# Copy_of_testboard_chip1_bk.net
KiCad netlist of a schematic drawn in Altium Designer
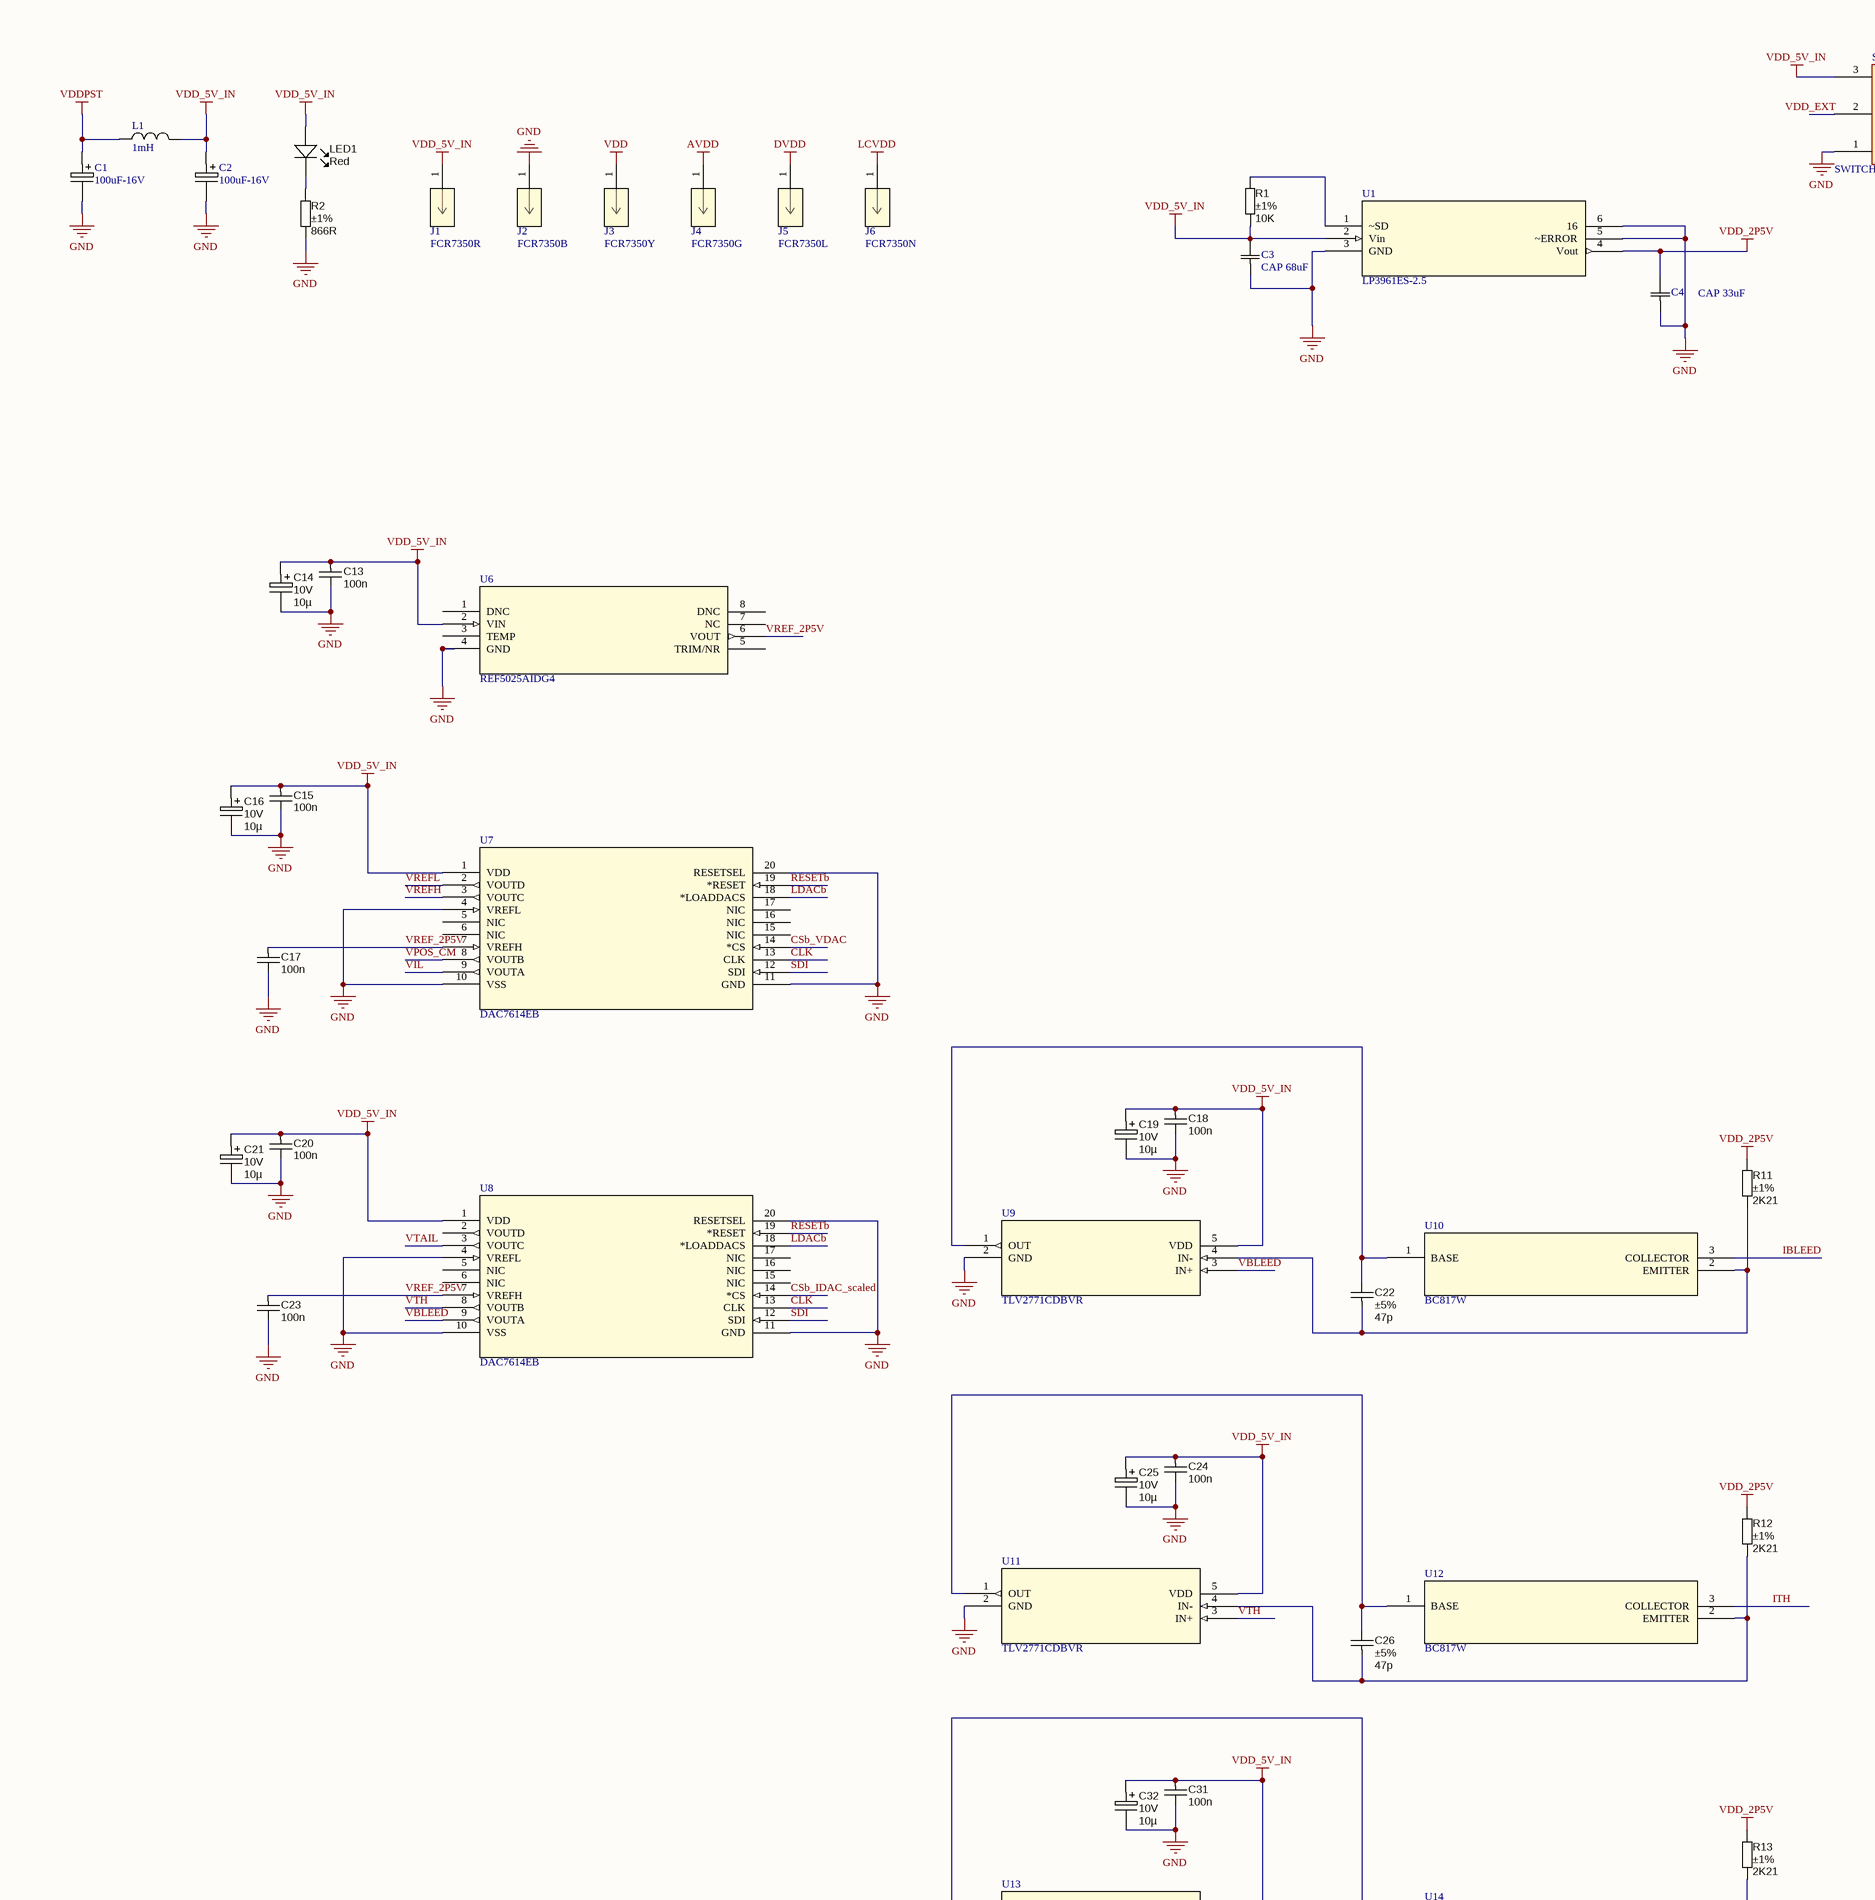
[diagram p0: Copy of testboard_chip1_bk.SchDoc, top left]
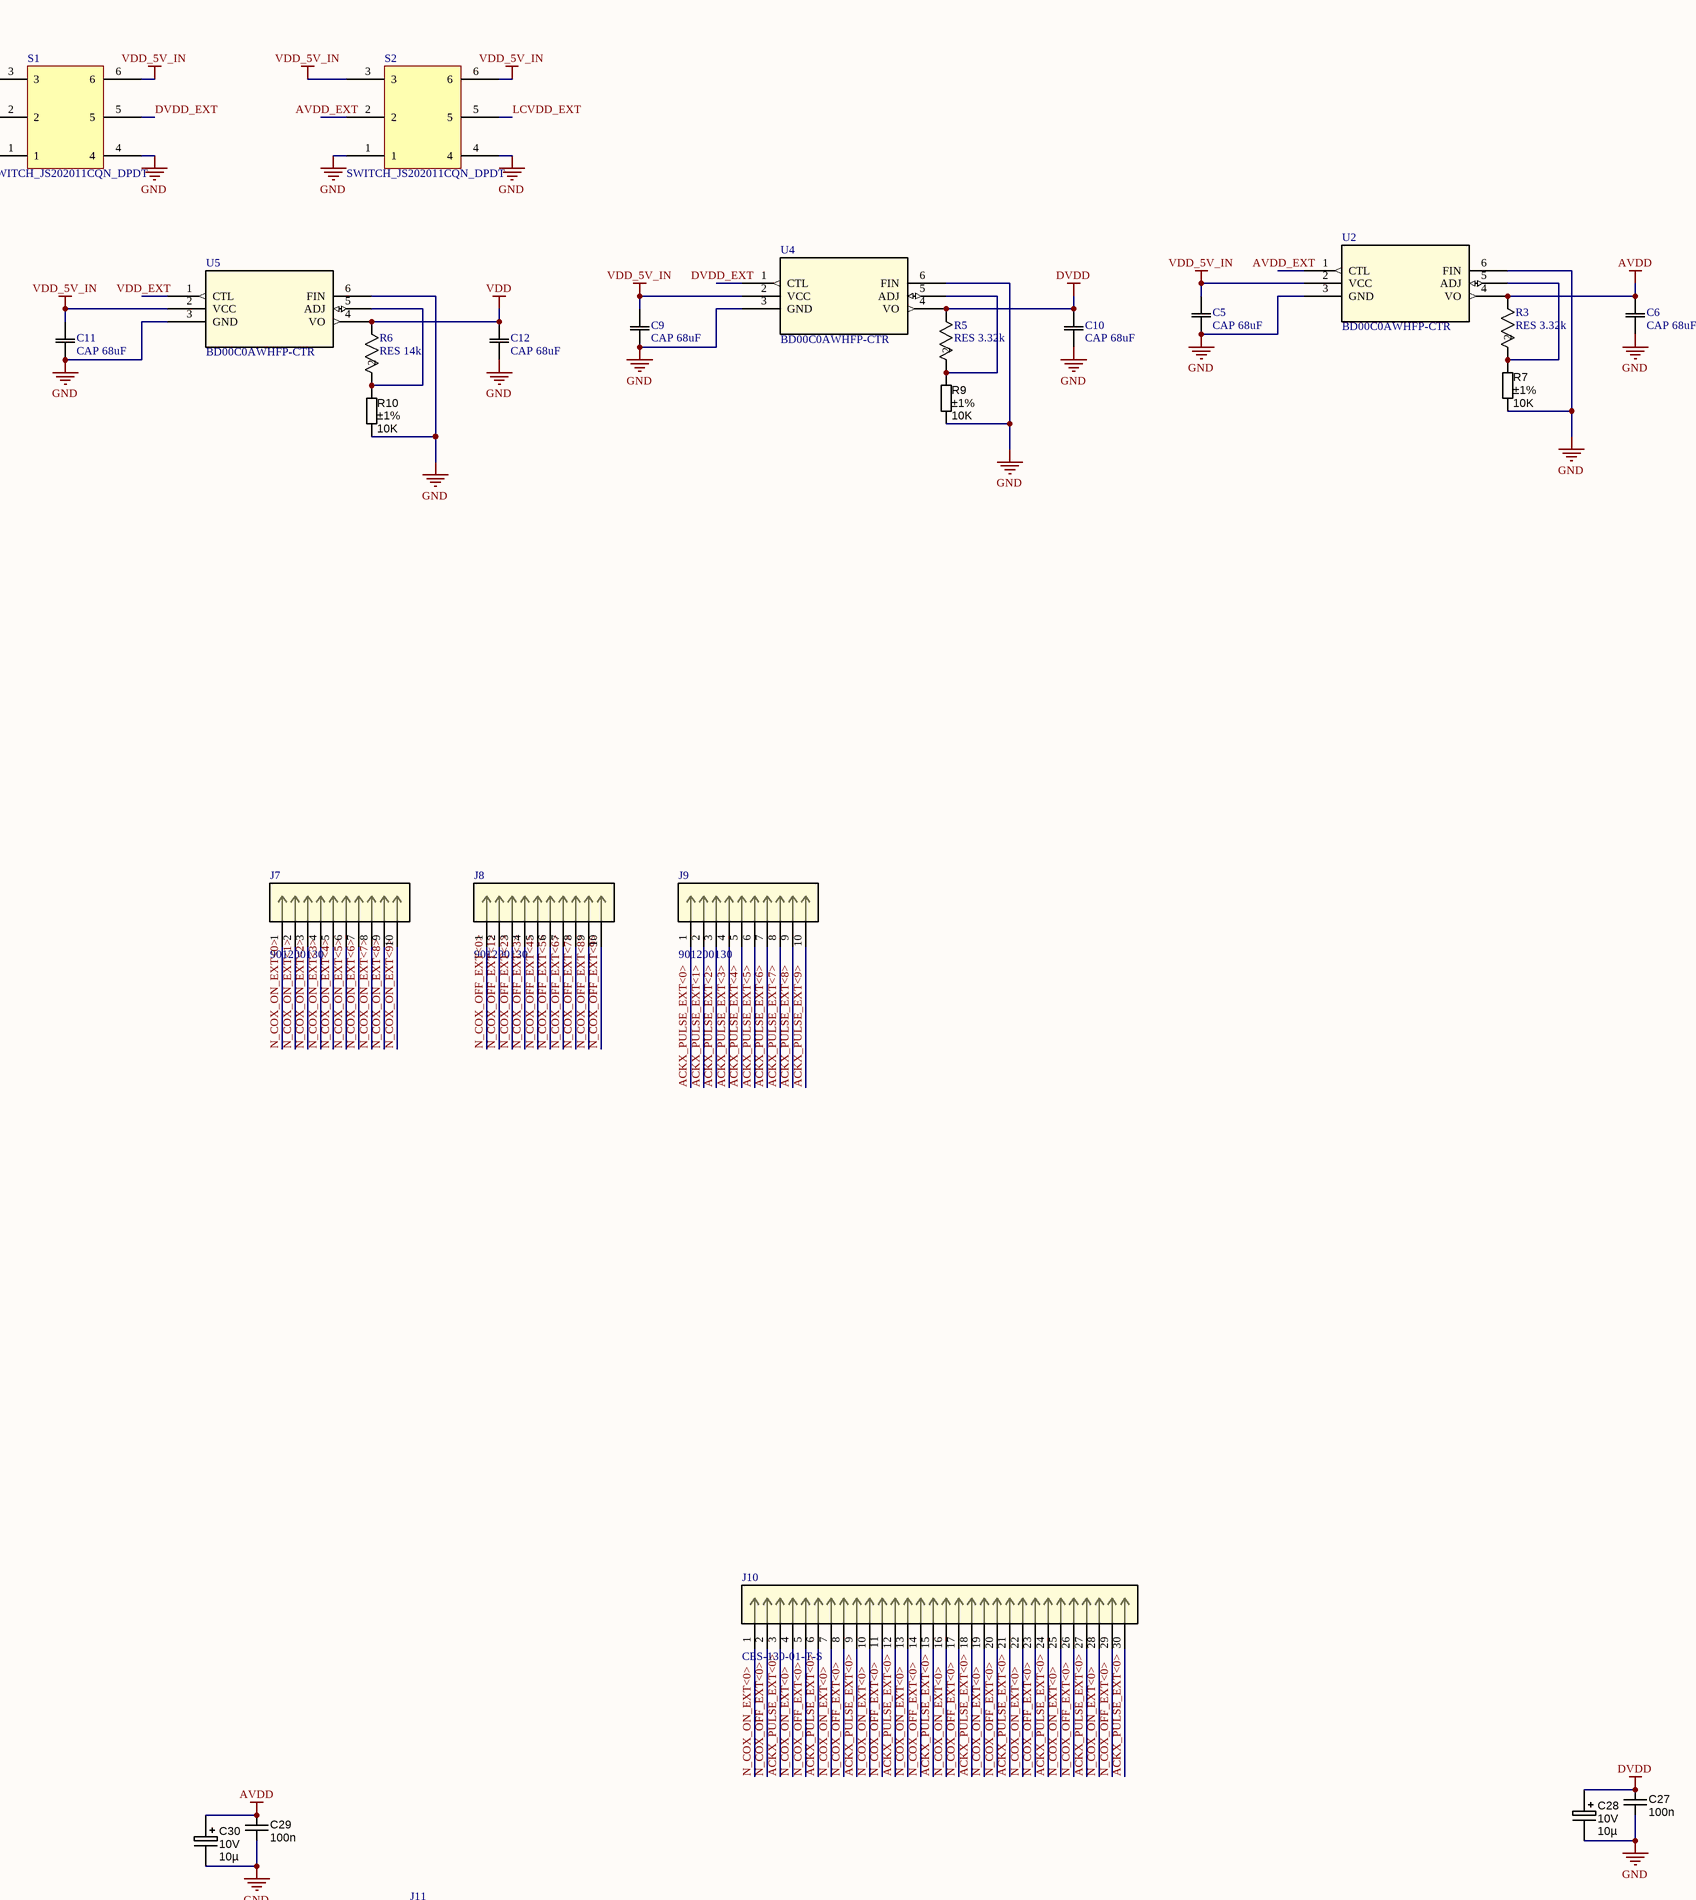
[diagram p1: Copy of testboard_chip1_bk.SchDoc, top middle]
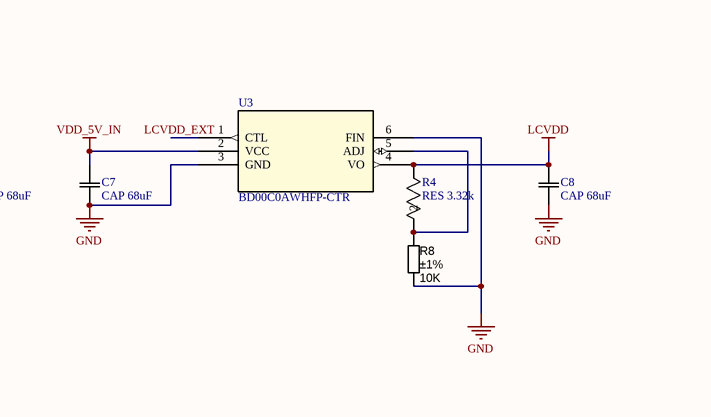
[diagram p2: Copy of testboard_chip1_bk.SchDoc, top right]
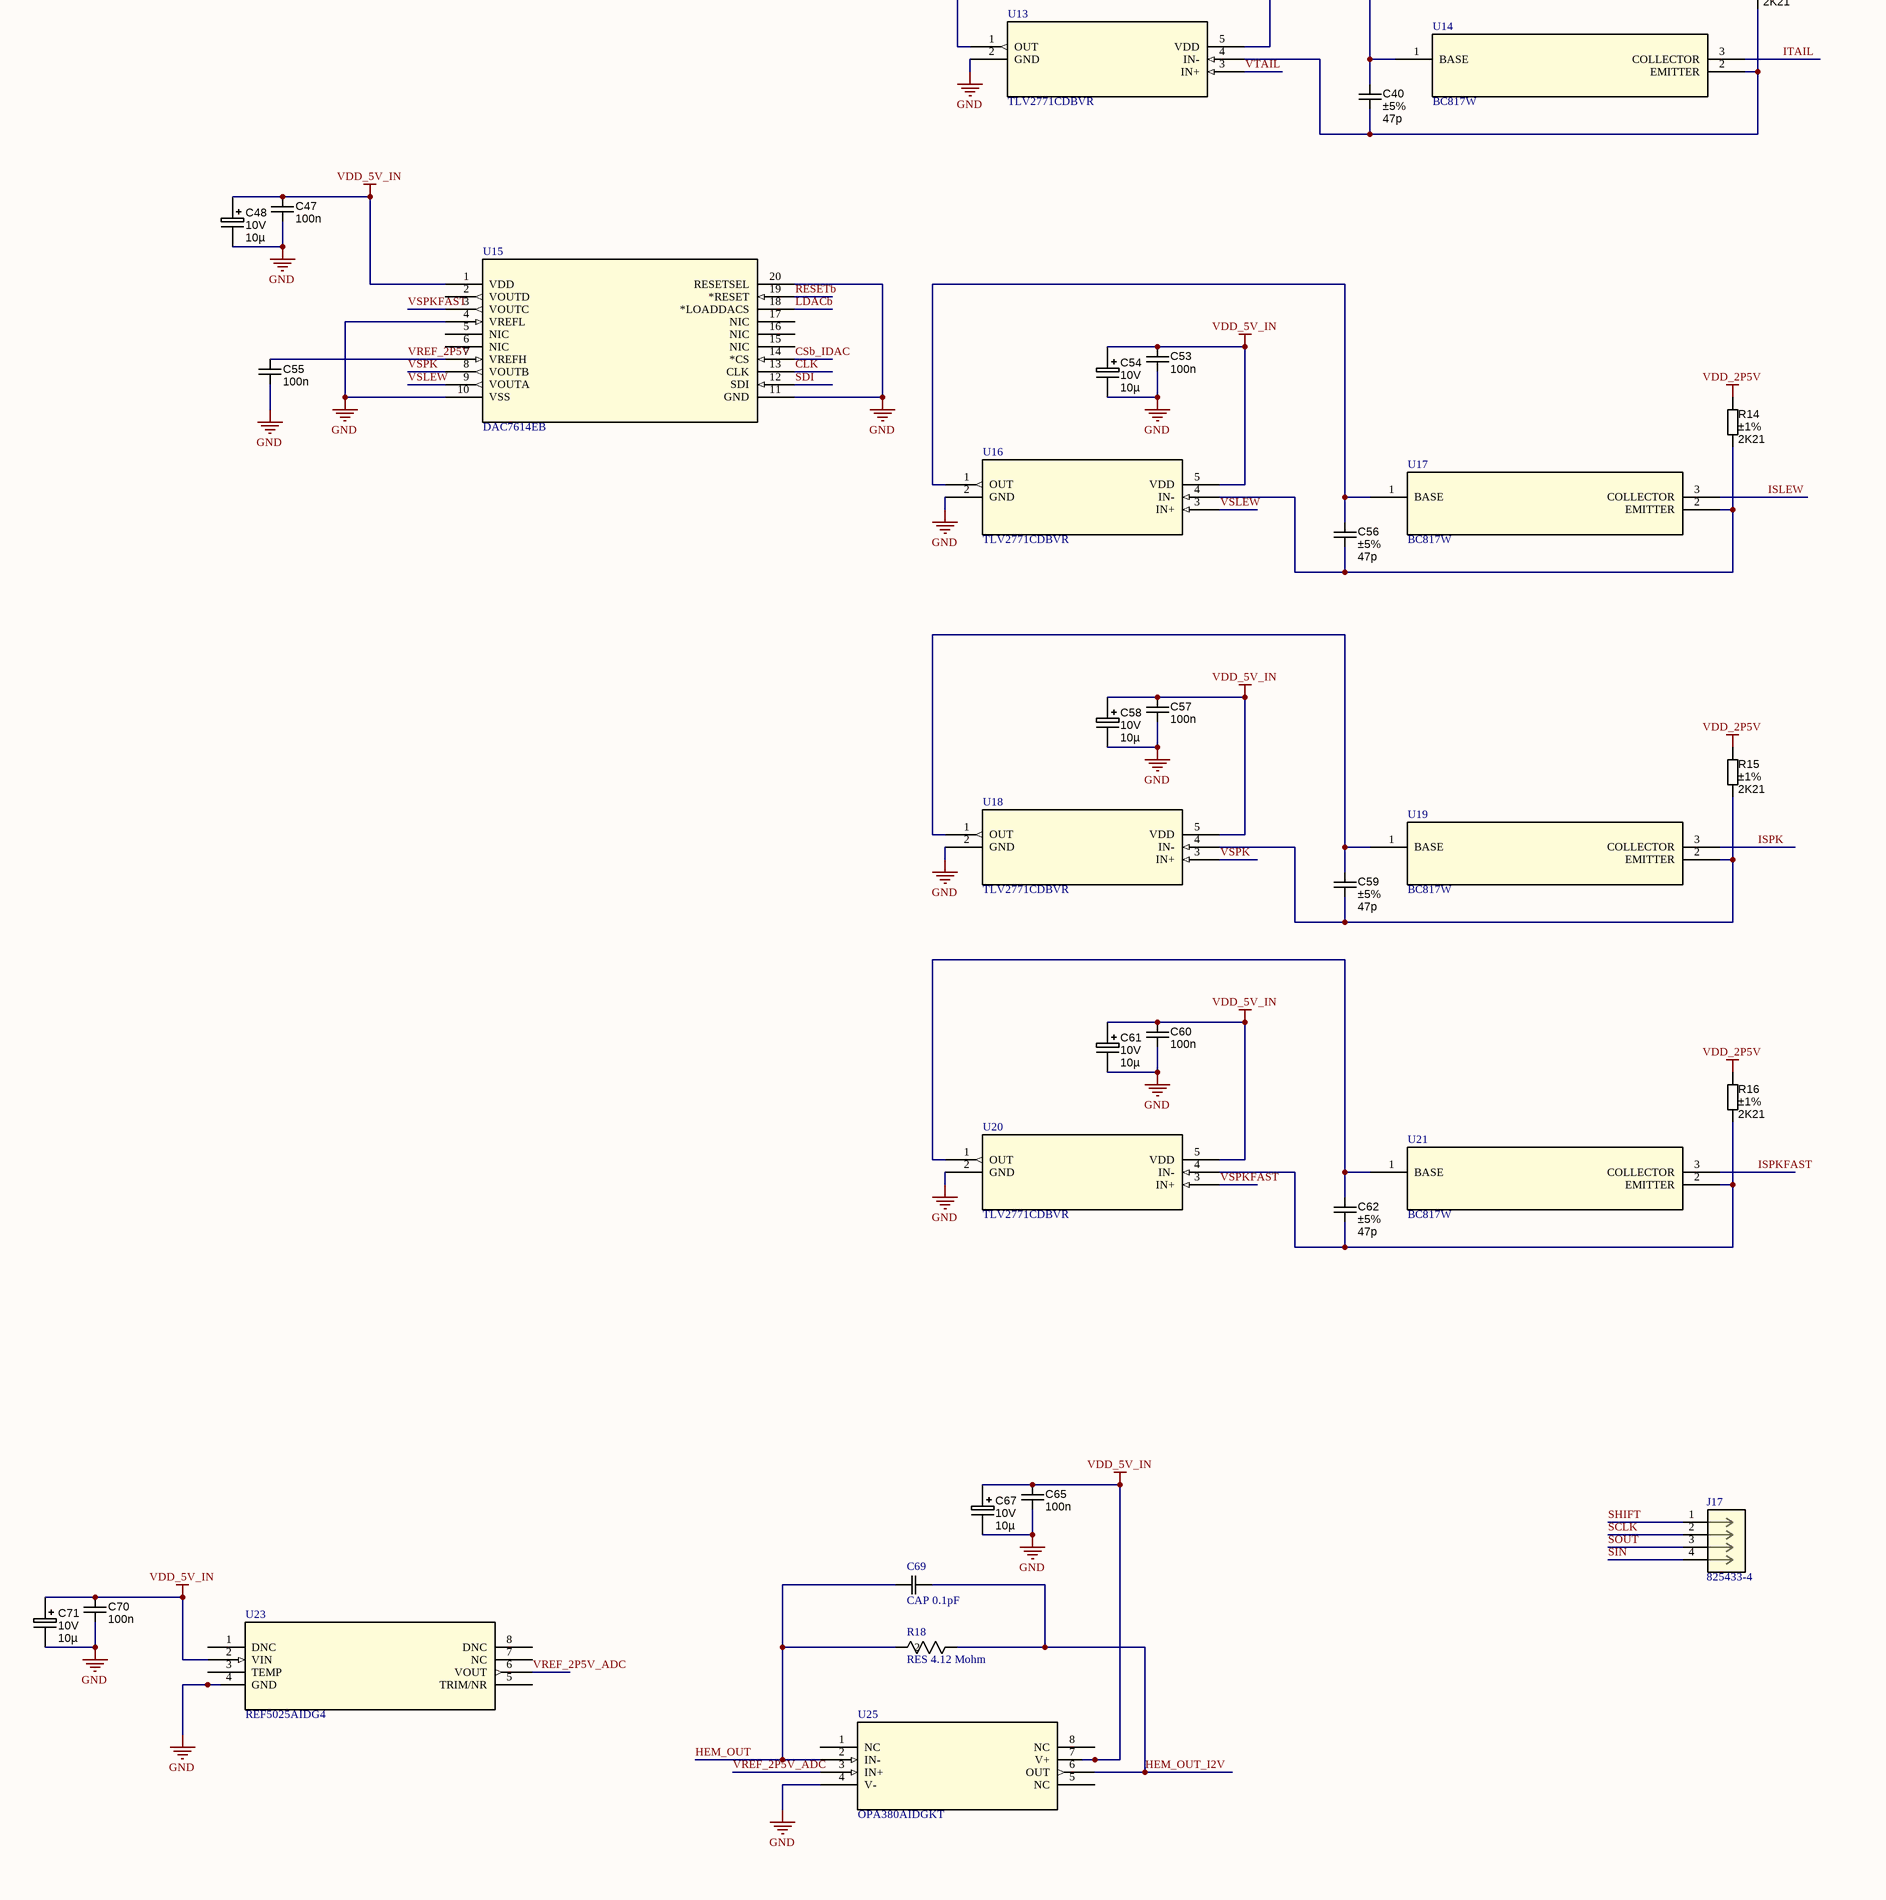
[diagram p3: Copy of testboard_chip1_bk.SchDoc, bottom left]
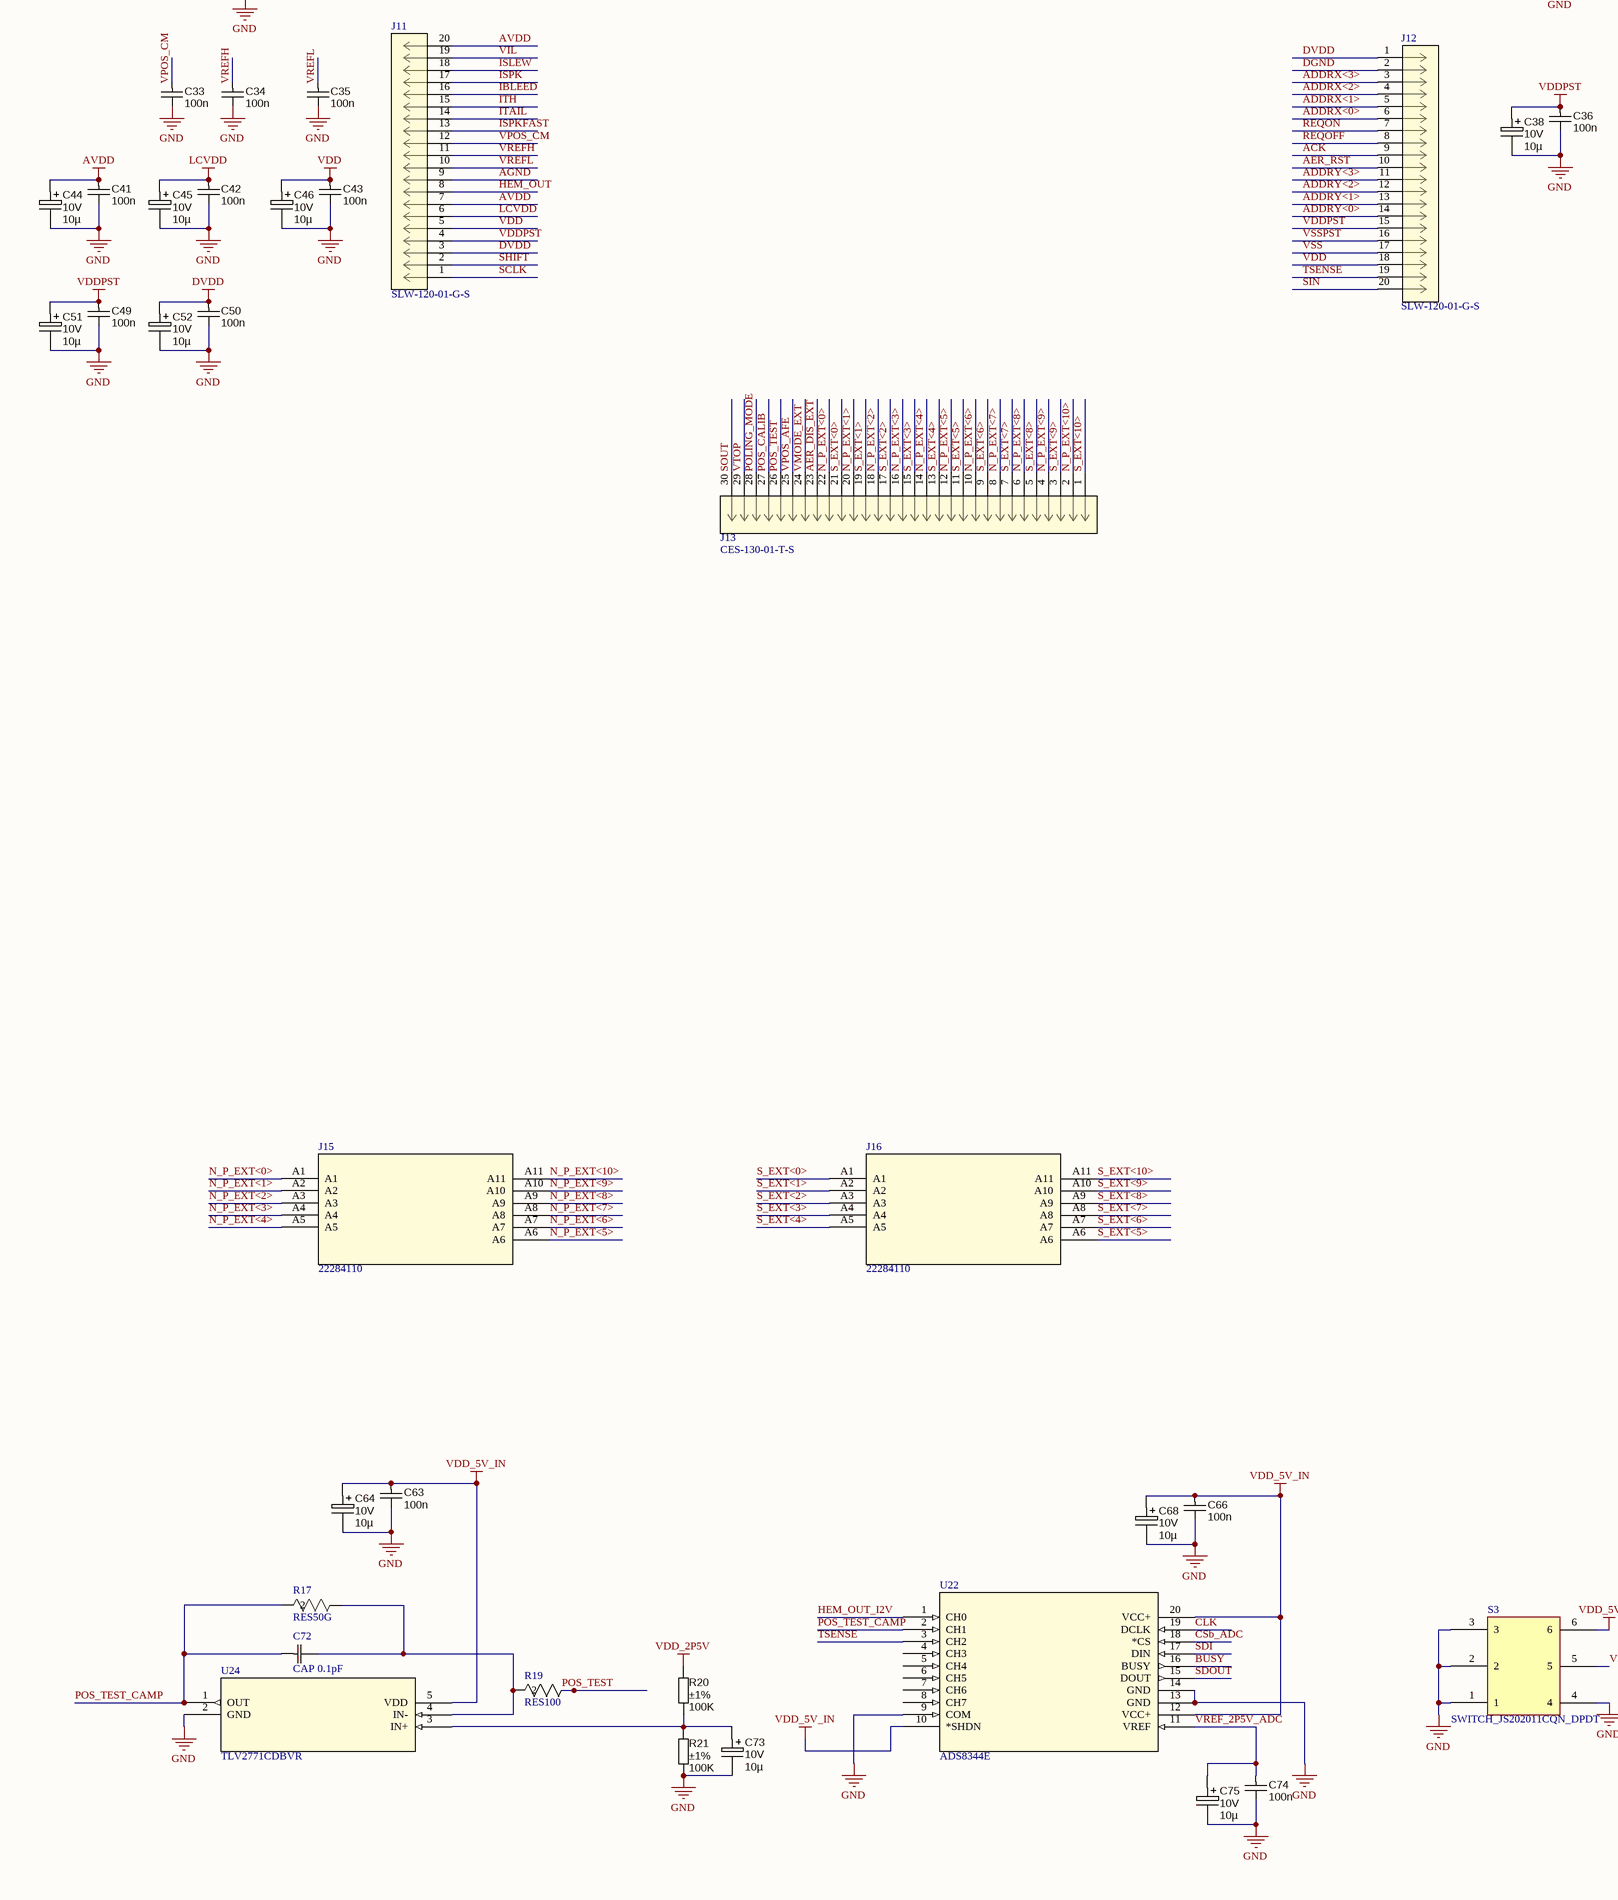
[diagram p4: Copy of testboard_chip1_bk.SchDoc, bottom middle]
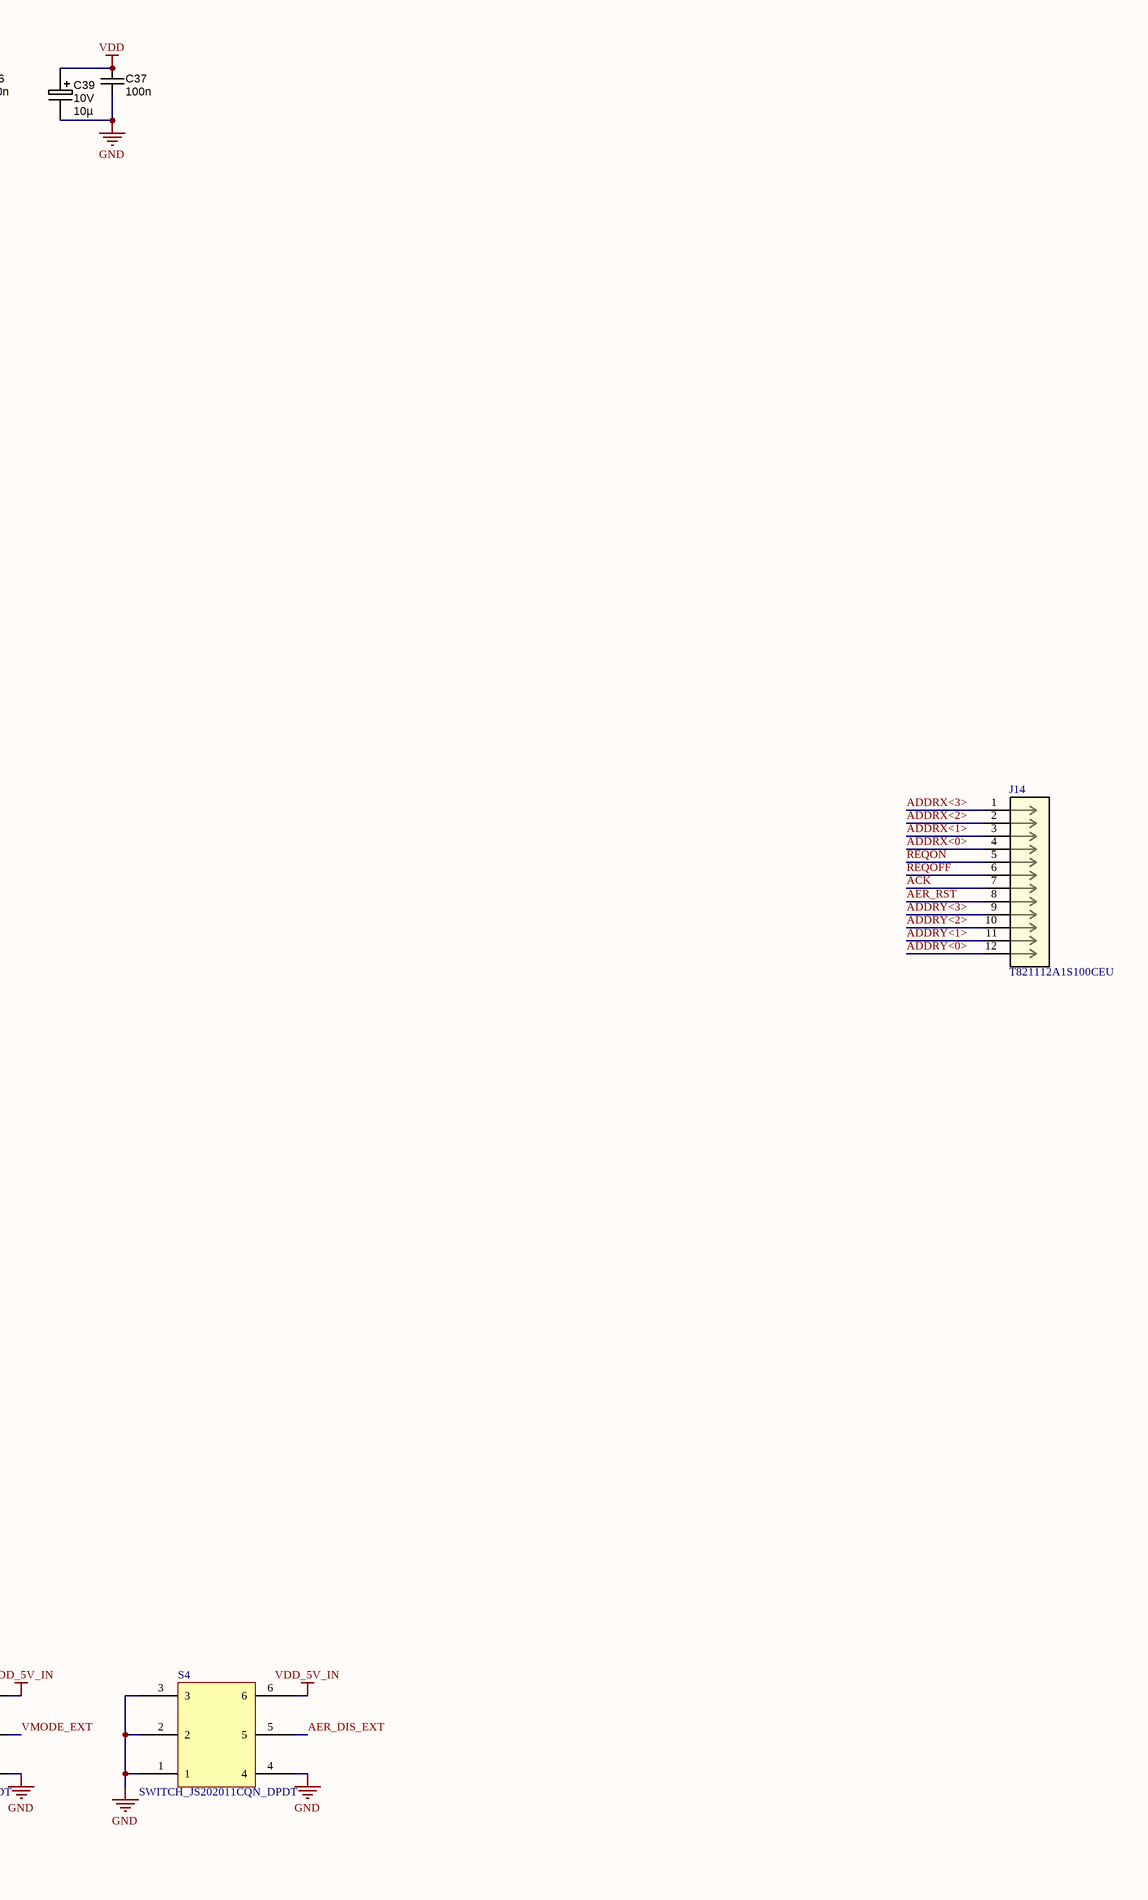
[diagram p5: Copy of testboard_chip1_bk.SchDoc, bottom right]

(export (version "E")
  (design (tool "Eeschema 10.0.6"))
  (components
    (comp (ref "C1")
      (value "100uF-16V")
      (footprint "PANACAP-D-GENERIC")
      (description "GENERIC CAPACITOR POLARISED")
      (libsource (lib "vh_altium_library") (part "PANACAP-100UF-16V-FK"))
    )
    (comp (ref "C2")
      (value "100uF-16V")
      (footprint "PANACAP-D-GENERIC")
      (description "GENERIC CAPACITOR POLARISED")
      (libsource (lib "vh_altium_library") (part "PANACAP-100UF-16V-FK"))
    )
    (comp (ref "C3")
      (value "CAP 68uF")
      (footprint "CAP_3216_TDK")
      (description "No Description Available")
      (fields
        (field (name "MANUFACTURER_PART_NUMBER") "C3216X5R1A686M160AC")
        (field (name "COPYRIGHT") "Copyright (C) 2022 Ultra Librarian. All rights reserved.")
      )
      (libsource (lib "C3216X5R1A686M160AC") (part "C3216X5R1A686M160AC"))
    )
    (comp (ref "C4")
      (value "CAP 33uF")
      (footprint "CAP_4532_TDK")
      (description "No Description Available")
      (fields
        (field (name "MANUFACTURER_PART_NUMBER") "C4532X7R1C336M250KC")
        (field (name "COPYRIGHT") "Copyright (C) 2022 Ultra Librarian. All rights reserved.")
      )
      (libsource (lib "C4532X7R1C336M250KC") (part "C4532X7R1C336M250KC"))
    )
    (comp (ref "C5")
      (value "CAP 68uF")
      (footprint "CAP_3216_TDK")
      (description "No Description Available")
      (fields
        (field (name "MANUFACTURER_PART_NUMBER") "C3216X5R1A686M160AC")
        (field (name "COPYRIGHT") "Copyright (C) 2022 Ultra Librarian. All rights reserved.")
      )
      (libsource (lib "C3216X5R1A686M160AC") (part "C3216X5R1A686M160AC"))
    )
    (comp (ref "C6")
      (value "CAP 68uF")
      (footprint "CAP_3216_TDK")
      (description "No Description Available")
      (fields
        (field (name "MANUFACTURER_PART_NUMBER") "C3216X5R1A686M160AC")
        (field (name "COPYRIGHT") "Copyright (C) 2022 Ultra Librarian. All rights reserved.")
      )
      (libsource (lib "C3216X5R1A686M160AC") (part "C3216X5R1A686M160AC"))
    )
    (comp (ref "C7")
      (value "CAP 68uF")
      (footprint "CAP_3216_TDK")
      (description "No Description Available")
      (fields
        (field (name "MANUFACTURER_PART_NUMBER") "C3216X5R1A686M160AC")
        (field (name "COPYRIGHT") "Copyright (C) 2022 Ultra Librarian. All rights reserved.")
      )
      (libsource (lib "C3216X5R1A686M160AC") (part "C3216X5R1A686M160AC"))
    )
    (comp (ref "C8")
      (value "CAP 68uF")
      (footprint "CAP_3216_TDK")
      (description "No Description Available")
      (fields
        (field (name "MANUFACTURER_PART_NUMBER") "C3216X5R1A686M160AC")
        (field (name "COPYRIGHT") "Copyright (C) 2022 Ultra Librarian. All rights reserved.")
      )
      (libsource (lib "C3216X5R1A686M160AC") (part "C3216X5R1A686M160AC"))
    )
    (comp (ref "C9")
      (value "CAP 68uF")
      (footprint "CAP_3216_TDK")
      (description "No Description Available")
      (fields
        (field (name "MANUFACTURER_PART_NUMBER") "C3216X5R1A686M160AC")
        (field (name "COPYRIGHT") "Copyright (C) 2022 Ultra Librarian. All rights reserved.")
      )
      (libsource (lib "C3216X5R1A686M160AC") (part "C3216X5R1A686M160AC"))
    )
    (comp (ref "C10")
      (value "CAP 68uF")
      (footprint "CAP_3216_TDK")
      (description "No Description Available")
      (fields
        (field (name "MANUFACTURER_PART_NUMBER") "C3216X5R1A686M160AC")
        (field (name "COPYRIGHT") "Copyright (C) 2022 Ultra Librarian. All rights reserved.")
      )
      (libsource (lib "C3216X5R1A686M160AC") (part "C3216X5R1A686M160AC"))
    )
    (comp (ref "C11")
      (value "CAP 68uF")
      (footprint "CAP_3216_TDK")
      (description "No Description Available")
      (fields
        (field (name "MANUFACTURER_PART_NUMBER") "C3216X5R1A686M160AC")
        (field (name "COPYRIGHT") "Copyright (C) 2022 Ultra Librarian. All rights reserved.")
      )
      (libsource (lib "C3216X5R1A686M160AC") (part "C3216X5R1A686M160AC"))
    )
    (comp (ref "C12")
      (value "CAP 68uF")
      (footprint "CAP_3216_TDK")
      (description "No Description Available")
      (fields
        (field (name "MANUFACTURER_PART_NUMBER") "C3216X5R1A686M160AC")
        (field (name "COPYRIGHT") "Copyright (C) 2022 Ultra Librarian. All rights reserved.")
      )
      (libsource (lib "C3216X5R1A686M160AC") (part "C3216X5R1A686M160AC"))
    )
    (comp (ref "C13")
      (value "100n")
      (footprint "CAPC1608N")
      (description "Capacitor SMD Cer 100nF 10% 50V X7R 0603")
      (fields (field (name "TOLERANCE") "±10%") (field (name "Comment") "approved sub OK"))
      (libsource (lib "PBL - Capacitors") (part "CAPC_100n_0603"))
    )
    (comp (ref "C14")
      (value "10µ")
      (footprint "CAPMP2012X150USR")
      (description "Capacitor SMD Tantalum 10uF 20% 10V 0805")
      (fields (field (name "TOLERANCE") "±20%") (field (name "RATINGS") "10V"))
      (libsource (lib "PBL - Capacitors") (part "CAPT_10u_0805_10V"))
    )
    (comp (ref "C15")
      (value "100n")
      (footprint "CAPC1608N")
      (description "Capacitor SMD Cer 100nF 10% 50V X7R 0603")
      (fields (field (name "TOLERANCE") "±10%") (field (name "Comment") "approved sub OK"))
      (libsource (lib "PBL - Capacitors") (part "CAPC_100n_0603"))
    )
    (comp (ref "C16")
      (value "10µ")
      (footprint "CAPMP2012X150USR")
      (description "Capacitor SMD Tantalum 10uF 20% 10V 0805")
      (fields (field (name "TOLERANCE") "±20%") (field (name "RATINGS") "10V"))
      (libsource (lib "PBL - Capacitors") (part "CAPT_10u_0805_10V"))
    )
    (comp (ref "C17")
      (value "100n")
      (footprint "CAPC1608N")
      (description "Capacitor SMD Cer 100nF 10% 50V X7R 0603")
      (fields (field (name "TOLERANCE") "±10%") (field (name "Comment") "approved sub OK"))
      (libsource (lib "PBL - Capacitors") (part "CAPC_100n_0603"))
    )
    (comp (ref "C18")
      (value "100n")
      (footprint "CAPC1608N")
      (description "Capacitor SMD Cer 100nF 10% 50V X7R 0603")
      (fields (field (name "TOLERANCE") "±10%") (field (name "Comment") "approved sub OK"))
      (libsource (lib "PBL - Capacitors") (part "CAPC_100n_0603"))
    )
    (comp (ref "C19")
      (value "10µ")
      (footprint "CAPMP2012X150USR")
      (description "Capacitor SMD Tantalum 10uF 20% 10V 0805")
      (fields (field (name "TOLERANCE") "±20%") (field (name "RATINGS") "10V"))
      (libsource (lib "PBL - Capacitors") (part "CAPT_10u_0805_10V"))
    )
    (comp (ref "C20")
      (value "100n")
      (footprint "CAPC1608N")
      (description "Capacitor SMD Cer 100nF 10% 50V X7R 0603")
      (fields (field (name "TOLERANCE") "±10%") (field (name "Comment") "approved sub OK"))
      (libsource (lib "PBL - Capacitors") (part "CAPC_100n_0603"))
    )
    (comp (ref "C21")
      (value "10µ")
      (footprint "CAPMP2012X150USR")
      (description "Capacitor SMD Tantalum 10uF 20% 10V 0805")
      (fields (field (name "TOLERANCE") "±20%") (field (name "RATINGS") "10V"))
      (libsource (lib "PBL - Capacitors") (part "CAPT_10u_0805_10V"))
    )
    (comp (ref "C22")
      (value "47p")
      (footprint "CAPC1608N")
      (description "Capacitor SMD Cer 47pF 0603")
      (fields (field (name "TOLERANCE") "±5%"))
      (libsource (lib "MB - Misc") (part "CAPC_47p_0603"))
    )
    (comp (ref "C23")
      (value "100n")
      (footprint "CAPC1608N")
      (description "Capacitor SMD Cer 100nF 10% 50V X7R 0603")
      (fields (field (name "TOLERANCE") "±10%") (field (name "Comment") "approved sub OK"))
      (libsource (lib "PBL - Capacitors") (part "CAPC_100n_0603"))
    )
    (comp (ref "C24")
      (value "100n")
      (footprint "CAPC1608N")
      (description "Capacitor SMD Cer 100nF 10% 50V X7R 0603")
      (fields (field (name "TOLERANCE") "±10%") (field (name "Comment") "approved sub OK"))
      (libsource (lib "PBL - Capacitors") (part "CAPC_100n_0603"))
    )
    (comp (ref "C25")
      (value "10µ")
      (footprint "CAPMP2012X150USR")
      (description "Capacitor SMD Tantalum 10uF 20% 10V 0805")
      (fields (field (name "TOLERANCE") "±20%") (field (name "RATINGS") "10V"))
      (libsource (lib "PBL - Capacitors") (part "CAPT_10u_0805_10V"))
    )
    (comp (ref "C26")
      (value "47p")
      (footprint "CAPC1608N")
      (description "Capacitor SMD Cer 47pF 0603")
      (fields (field (name "TOLERANCE") "±5%"))
      (libsource (lib "MB - Misc") (part "CAPC_47p_0603"))
    )
    (comp (ref "C27")
      (value "100n")
      (footprint "CAPC1608N")
      (description "Capacitor SMD Cer 100nF 10% 50V X7R 0603")
      (fields (field (name "TOLERANCE") "±10%") (field (name "Comment") "approved sub OK"))
      (libsource (lib "PBL - Capacitors") (part "CAPC_100n_0603"))
    )
    (comp (ref "C28")
      (value "10µ")
      (footprint "CAPMP2012X150USR")
      (description "Capacitor SMD Tantalum 10uF 20% 10V 0805")
      (fields (field (name "TOLERANCE") "±20%") (field (name "RATINGS") "10V"))
      (libsource (lib "PBL - Capacitors") (part "CAPT_10u_0805_10V"))
    )
    (comp (ref "C29")
      (value "100n")
      (footprint "CAPC1608N")
      (description "Capacitor SMD Cer 100nF 10% 50V X7R 0603")
      (fields (field (name "TOLERANCE") "±10%") (field (name "Comment") "approved sub OK"))
      (libsource (lib "PBL - Capacitors") (part "CAPC_100n_0603"))
    )
    (comp (ref "C30")
      (value "10µ")
      (footprint "CAPMP2012X150USR")
      (description "Capacitor SMD Tantalum 10uF 20% 10V 0805")
      (fields (field (name "TOLERANCE") "±20%") (field (name "RATINGS") "10V"))
      (libsource (lib "PBL - Capacitors") (part "CAPT_10u_0805_10V"))
    )
    (comp (ref "C31")
      (value "100n")
      (footprint "CAPC1608N")
      (description "Capacitor SMD Cer 100nF 10% 50V X7R 0603")
      (fields (field (name "TOLERANCE") "±10%") (field (name "Comment") "approved sub OK"))
      (libsource (lib "PBL - Capacitors") (part "CAPC_100n_0603"))
    )
    (comp (ref "C32")
      (value "10µ")
      (footprint "CAPMP2012X150USR")
      (description "Capacitor SMD Tantalum 10uF 20% 10V 0805")
      (fields (field (name "TOLERANCE") "±20%") (field (name "RATINGS") "10V"))
      (libsource (lib "PBL - Capacitors") (part "CAPT_10u_0805_10V"))
    )
    (comp (ref "C33")
      (value "100n")
      (footprint "CAPC1608N")
      (description "Capacitor SMD Cer 100nF 10% 50V X7R 0603")
      (fields (field (name "TOLERANCE") "±10%") (field (name "Comment") "approved sub OK"))
      (libsource (lib "PBL - Capacitors") (part "CAPC_100n_0603"))
    )
    (comp (ref "C34")
      (value "100n")
      (footprint "CAPC1608N")
      (description "Capacitor SMD Cer 100nF 10% 50V X7R 0603")
      (fields (field (name "TOLERANCE") "±10%") (field (name "Comment") "approved sub OK"))
      (libsource (lib "PBL - Capacitors") (part "CAPC_100n_0603"))
    )
    (comp (ref "C35")
      (value "100n")
      (footprint "CAPC1608N")
      (description "Capacitor SMD Cer 100nF 10% 50V X7R 0603")
      (fields (field (name "TOLERANCE") "±10%") (field (name "Comment") "approved sub OK"))
      (libsource (lib "PBL - Capacitors") (part "CAPC_100n_0603"))
    )
    (comp (ref "C36")
      (value "100n")
      (footprint "CAPC1608N")
      (description "Capacitor SMD Cer 100nF 10% 50V X7R 0603")
      (fields (field (name "TOLERANCE") "±10%") (field (name "Comment") "approved sub OK"))
      (libsource (lib "PBL - Capacitors") (part "CAPC_100n_0603"))
    )
    (comp (ref "C37")
      (value "100n")
      (footprint "CAPC1608N")
      (description "Capacitor SMD Cer 100nF 10% 50V X7R 0603")
      (fields (field (name "TOLERANCE") "±10%") (field (name "Comment") "approved sub OK"))
      (libsource (lib "PBL - Capacitors") (part "CAPC_100n_0603"))
    )
    (comp (ref "C38")
      (value "10µ")
      (footprint "CAPMP2012X150USR")
      (description "Capacitor SMD Tantalum 10uF 20% 10V 0805")
      (fields (field (name "TOLERANCE") "±20%") (field (name "RATINGS") "10V"))
      (libsource (lib "PBL - Capacitors") (part "CAPT_10u_0805_10V"))
    )
    (comp (ref "C39")
      (value "10µ")
      (footprint "CAPMP2012X150USR")
      (description "Capacitor SMD Tantalum 10uF 20% 10V 0805")
      (fields (field (name "TOLERANCE") "±20%") (field (name "RATINGS") "10V"))
      (libsource (lib "PBL - Capacitors") (part "CAPT_10u_0805_10V"))
    )
    (comp (ref "C40")
      (value "47p")
      (footprint "CAPC1608N")
      (description "Capacitor SMD Cer 47pF 0603")
      (fields (field (name "TOLERANCE") "±5%"))
      (libsource (lib "MB - Misc") (part "CAPC_47p_0603"))
    )
    (comp (ref "C41")
      (value "100n")
      (footprint "CAPC1608N")
      (description "Capacitor SMD Cer 100nF 10% 50V X7R 0603")
      (fields (field (name "TOLERANCE") "±10%") (field (name "Comment") "approved sub OK"))
      (libsource (lib "PBL - Capacitors") (part "CAPC_100n_0603"))
    )
    (comp (ref "C42")
      (value "100n")
      (footprint "CAPC1608N")
      (description "Capacitor SMD Cer 100nF 10% 50V X7R 0603")
      (fields (field (name "TOLERANCE") "±10%") (field (name "Comment") "approved sub OK"))
      (libsource (lib "PBL - Capacitors") (part "CAPC_100n_0603"))
    )
    (comp (ref "C43")
      (value "100n")
      (footprint "CAPC1608N")
      (description "Capacitor SMD Cer 100nF 10% 50V X7R 0603")
      (fields (field (name "TOLERANCE") "±10%") (field (name "Comment") "approved sub OK"))
      (libsource (lib "PBL - Capacitors") (part "CAPC_100n_0603"))
    )
    (comp (ref "C44")
      (value "10µ")
      (footprint "CAPMP2012X150USR")
      (description "Capacitor SMD Tantalum 10uF 20% 10V 0805")
      (fields (field (name "TOLERANCE") "±20%") (field (name "RATINGS") "10V"))
      (libsource (lib "PBL - Capacitors") (part "CAPT_10u_0805_10V"))
    )
    (comp (ref "C45")
      (value "10µ")
      (footprint "CAPMP2012X150USR")
      (description "Capacitor SMD Tantalum 10uF 20% 10V 0805")
      (fields (field (name "TOLERANCE") "±20%") (field (name "RATINGS") "10V"))
      (libsource (lib "PBL - Capacitors") (part "CAPT_10u_0805_10V"))
    )
    (comp (ref "C46")
      (value "10µ")
      (footprint "CAPMP2012X150USR")
      (description "Capacitor SMD Tantalum 10uF 20% 10V 0805")
      (fields (field (name "TOLERANCE") "±20%") (field (name "RATINGS") "10V"))
      (libsource (lib "PBL - Capacitors") (part "CAPT_10u_0805_10V"))
    )
    (comp (ref "C47")
      (value "100n")
      (footprint "CAPC1608N")
      (description "Capacitor SMD Cer 100nF 10% 50V X7R 0603")
      (fields (field (name "TOLERANCE") "±10%") (field (name "Comment") "approved sub OK"))
      (libsource (lib "PBL - Capacitors") (part "CAPC_100n_0603"))
    )
    (comp (ref "C48")
      (value "10µ")
      (footprint "CAPMP2012X150USR")
      (description "Capacitor SMD Tantalum 10uF 20% 10V 0805")
      (fields (field (name "TOLERANCE") "±20%") (field (name "RATINGS") "10V"))
      (libsource (lib "PBL - Capacitors") (part "CAPT_10u_0805_10V"))
    )
    (comp (ref "C49")
      (value "100n")
      (footprint "CAPC1608N")
      (description "Capacitor SMD Cer 100nF 10% 50V X7R 0603")
      (fields (field (name "TOLERANCE") "±10%") (field (name "Comment") "approved sub OK"))
      (libsource (lib "PBL - Capacitors") (part "CAPC_100n_0603"))
    )
    (comp (ref "C50")
      (value "100n")
      (footprint "CAPC1608N")
      (description "Capacitor SMD Cer 100nF 10% 50V X7R 0603")
      (fields (field (name "TOLERANCE") "±10%") (field (name "Comment") "approved sub OK"))
      (libsource (lib "PBL - Capacitors") (part "CAPC_100n_0603"))
    )
    (comp (ref "C51")
      (value "10µ")
      (footprint "CAPMP2012X150USR")
      (description "Capacitor SMD Tantalum 10uF 20% 10V 0805")
      (fields (field (name "TOLERANCE") "±20%") (field (name "RATINGS") "10V"))
      (libsource (lib "PBL - Capacitors") (part "CAPT_10u_0805_10V"))
    )
    (comp (ref "C52")
      (value "10µ")
      (footprint "CAPMP2012X150USR")
      (description "Capacitor SMD Tantalum 10uF 20% 10V 0805")
      (fields (field (name "TOLERANCE") "±20%") (field (name "RATINGS") "10V"))
      (libsource (lib "PBL - Capacitors") (part "CAPT_10u_0805_10V"))
    )
    (comp (ref "C53")
      (value "100n")
      (footprint "CAPC1608N")
      (description "Capacitor SMD Cer 100nF 10% 50V X7R 0603")
      (fields (field (name "TOLERANCE") "±10%") (field (name "Comment") "approved sub OK"))
      (libsource (lib "PBL - Capacitors") (part "CAPC_100n_0603"))
    )
    (comp (ref "C54")
      (value "10µ")
      (footprint "CAPMP2012X150USR")
      (description "Capacitor SMD Tantalum 10uF 20% 10V 0805")
      (fields (field (name "TOLERANCE") "±20%") (field (name "RATINGS") "10V"))
      (libsource (lib "PBL - Capacitors") (part "CAPT_10u_0805_10V"))
    )
    (comp (ref "C55")
      (value "100n")
      (footprint "CAPC1608N")
      (description "Capacitor SMD Cer 100nF 10% 50V X7R 0603")
      (fields (field (name "TOLERANCE") "±10%") (field (name "Comment") "approved sub OK"))
      (libsource (lib "PBL - Capacitors") (part "CAPC_100n_0603"))
    )
    (comp (ref "C56")
      (value "47p")
      (footprint "CAPC1608N")
      (description "Capacitor SMD Cer 47pF 0603")
      (fields (field (name "TOLERANCE") "±5%"))
      (libsource (lib "MB - Misc") (part "CAPC_47p_0603"))
    )
    (comp (ref "C57")
      (value "100n")
      (footprint "CAPC1608N")
      (description "Capacitor SMD Cer 100nF 10% 50V X7R 0603")
      (fields (field (name "TOLERANCE") "±10%") (field (name "Comment") "approved sub OK"))
      (libsource (lib "PBL - Capacitors") (part "CAPC_100n_0603"))
    )
    (comp (ref "C58")
      (value "10µ")
      (footprint "CAPMP2012X150USR")
      (description "Capacitor SMD Tantalum 10uF 20% 10V 0805")
      (fields (field (name "TOLERANCE") "±20%") (field (name "RATINGS") "10V"))
      (libsource (lib "PBL - Capacitors") (part "CAPT_10u_0805_10V"))
    )
    (comp (ref "C59")
      (value "47p")
      (footprint "CAPC1608N")
      (description "Capacitor SMD Cer 47pF 0603")
      (fields (field (name "TOLERANCE") "±5%"))
      (libsource (lib "MB - Misc") (part "CAPC_47p_0603"))
    )
    (comp (ref "C60")
      (value "100n")
      (footprint "CAPC1608N")
      (description "Capacitor SMD Cer 100nF 10% 50V X7R 0603")
      (fields (field (name "TOLERANCE") "±10%") (field (name "Comment") "approved sub OK"))
      (libsource (lib "PBL - Capacitors") (part "CAPC_100n_0603"))
    )
    (comp (ref "C61")
      (value "10µ")
      (footprint "CAPMP2012X150USR")
      (description "Capacitor SMD Tantalum 10uF 20% 10V 0805")
      (fields (field (name "TOLERANCE") "±20%") (field (name "RATINGS") "10V"))
      (libsource (lib "PBL - Capacitors") (part "CAPT_10u_0805_10V"))
    )
    (comp (ref "C62")
      (value "47p")
      (footprint "CAPC1608N")
      (description "Capacitor SMD Cer 47pF 0603")
      (fields (field (name "TOLERANCE") "±5%"))
      (libsource (lib "MB - Misc") (part "CAPC_47p_0603"))
    )
    (comp (ref "C63")
      (value "100n")
      (footprint "CAPC1608N")
      (description "Capacitor SMD Cer 100nF 10% 50V X7R 0603")
      (fields (field (name "TOLERANCE") "±10%") (field (name "Comment") "approved sub OK"))
      (libsource (lib "PBL - Capacitors") (part "CAPC_100n_0603"))
    )
    (comp (ref "C64")
      (value "10µ")
      (footprint "CAPMP2012X150USR")
      (description "Capacitor SMD Tantalum 10uF 20% 10V 0805")
      (fields (field (name "TOLERANCE") "±20%") (field (name "RATINGS") "10V"))
      (libsource (lib "PBL - Capacitors") (part "CAPT_10u_0805_10V"))
    )
    (comp (ref "C65")
      (value "100n")
      (footprint "CAPC1608N")
      (description "Capacitor SMD Cer 100nF 10% 50V X7R 0603")
      (fields (field (name "TOLERANCE") "±10%") (field (name "Comment") "approved sub OK"))
      (libsource (lib "PBL - Capacitors") (part "CAPC_100n_0603"))
    )
    (comp (ref "C66")
      (value "100n")
      (footprint "CAPC1608N")
      (description "Capacitor SMD Cer 100nF 10% 50V X7R 0603")
      (fields (field (name "TOLERANCE") "±10%") (field (name "Comment") "approved sub OK"))
      (libsource (lib "PBL - Capacitors") (part "CAPC_100n_0603"))
    )
    (comp (ref "C67")
      (value "10µ")
      (footprint "CAPMP2012X150USR")
      (description "Capacitor SMD Tantalum 10uF 20% 10V 0805")
      (fields (field (name "TOLERANCE") "±20%") (field (name "RATINGS") "10V"))
      (libsource (lib "PBL - Capacitors") (part "CAPT_10u_0805_10V"))
    )
    (comp (ref "C68")
      (value "10µ")
      (footprint "CAPMP2012X150USR")
      (description "Capacitor SMD Tantalum 10uF 20% 10V 0805")
      (fields (field (name "TOLERANCE") "±20%") (field (name "RATINGS") "10V"))
      (libsource (lib "PBL - Capacitors") (part "CAPT_10u_0805_10V"))
    )
    (comp (ref "C69")
      (value "CAP 0.1pF")
      (footprint "CAP_0603_AVX")
      (description "No Description Available")
      (fields
        (field (name "MANUFACTURER_PART_NUMBER") "ML03V10R1AAT2A")
        (field (name "COPYRIGHT") "Copyright (C) 2022 Ultra Librarian. All rights reserved.")
      )
      (libsource (lib "ML03V10R1AAT2A") (part "ML03V10R1AAT2A"))
    )
    (comp (ref "C70")
      (value "100n")
      (footprint "CAPC1608N")
      (description "Capacitor SMD Cer 100nF 10% 50V X7R 0603")
      (fields (field (name "TOLERANCE") "±10%") (field (name "Comment") "approved sub OK"))
      (libsource (lib "PBL - Capacitors") (part "CAPC_100n_0603"))
    )
    (comp (ref "C71")
      (value "10µ")
      (footprint "CAPMP2012X150USR")
      (description "Capacitor SMD Tantalum 10uF 20% 10V 0805")
      (fields (field (name "TOLERANCE") "±20%") (field (name "RATINGS") "10V"))
      (libsource (lib "PBL - Capacitors") (part "CAPT_10u_0805_10V"))
    )
    (comp (ref "C72")
      (value "CAP 0.1pF")
      (footprint "CAP_0603_AVX")
      (description "No Description Available")
      (fields
        (field (name "MANUFACTURER_PART_NUMBER") "ML03V10R1AAT2A")
        (field (name "COPYRIGHT") "Copyright (C) 2022 Ultra Librarian. All rights reserved.")
      )
      (libsource (lib "ML03V10R1AAT2A") (part "ML03V10R1AAT2A"))
    )
    (comp (ref "C73")
      (value "10µ")
      (footprint "CAPMP2012X150USR")
      (description "Capacitor SMD Tantalum 10uF 20% 10V 0805")
      (fields (field (name "TOLERANCE") "±20%") (field (name "RATINGS") "10V"))
      (libsource (lib "PBL - Capacitors") (part "CAPT_10u_0805_10V"))
    )
    (comp (ref "C74")
      (value "100n")
      (footprint "CAPC1608N")
      (description "Capacitor SMD Cer 100nF 10% 50V X7R 0603")
      (fields (field (name "TOLERANCE") "±10%") (field (name "Comment") "approved sub OK"))
      (libsource (lib "PBL - Capacitors") (part "CAPC_100n_0603"))
    )
    (comp (ref "C75")
      (value "10µ")
      (footprint "CAPMP2012X150USR")
      (description "Capacitor SMD Tantalum 10uF 20% 10V 0805")
      (fields (field (name "TOLERANCE") "±20%") (field (name "RATINGS") "10V"))
      (libsource (lib "PBL - Capacitors") (part "CAPT_10u_0805_10V"))
    )
    (comp (ref "J1")
      (value "FCR7350R")
      (footprint "CONN1_FCR7350R_CLF")
      (description "No Description Available")
      (fields (field (name "COPYRIGHT") "Copyright (C) 2022 Ultra Librarian. All rights reserved."))
      (libsource (lib "FCR7350R") (part "FCR7350R"))
    )
    (comp (ref "J2")
      (value "FCR7350B")
      (footprint "CONN1_FCR7350R_CLF")
      (description "No Description Available")
      (fields
        (field (name "MANUFACTURER_PART_NUMBER") "FCR7350R")
        (field (name "COPYRIGHT") "Copyright (C) 2022 Ultra Librarian. All rights reserved.")
      )
      (libsource (lib "FCR7350B") (part "FCR7350R"))
    )
    (comp (ref "J3")
      (value "FCR7350Y")
      (footprint "CONN1_FCR7350R_CLF")
      (description "No Description Available")
      (fields
        (field (name "MANUFACTURER_PART_NUMBER") "FCR7350R")
        (field (name "COPYRIGHT") "Copyright (C) 2022 Ultra Librarian. All rights reserved.")
      )
      (libsource (lib "FCR7350Y") (part "FCR7350R"))
    )
    (comp (ref "J4")
      (value "FCR7350G")
      (footprint "CONN_FCR7350G_CLF")
      (description "No Description Available")
      (fields (field (name "COPYRIGHT") "Copyright (C) 2022 Ultra Librarian. All rights reserved."))
      (libsource (lib "FCR7350G") (part "FCR7350G"))
    )
    (comp (ref "J5")
      (value "FCR7350L")
      (footprint "CONN1_FCR7350R_CLF")
      (description "No Description Available")
      (fields
        (field (name "MANUFACTURER_PART_NUMBER") "FCR7350R")
        (field (name "COPYRIGHT") "Copyright (C) 2022 Ultra Librarian. All rights reserved.")
      )
      (libsource (lib "FCR7350L") (part "FCR7350R"))
    )
    (comp (ref "J6")
      (value "FCR7350N")
      (footprint "CONN1_FCR7350R_CLF")
      (description "No Description Available")
      (fields
        (field (name "MANUFACTURER_PART_NUMBER") "FCR7350R")
        (field (name "COPYRIGHT") "Copyright (C) 2022 Ultra Librarian. All rights reserved.")
      )
      (libsource (lib "FCR7350N") (part "FCR7350R"))
    )
    (comp (ref "J7")
      (value "901200130")
      (footprint "CON_901200130_MOL")
      (description "No Description Available")
      (fields (field (name "COPYRIGHT") "Copyright (C) 2022 Ultra Librarian. All rights reserved."))
      (libsource (lib "901200130") (part "901200130"))
    )
    (comp (ref "J8")
      (value "901200130")
      (footprint "CON_901200130_MOL")
      (description "No Description Available")
      (fields (field (name "COPYRIGHT") "Copyright (C) 2022 Ultra Librarian. All rights reserved."))
      (libsource (lib "901200130") (part "901200130"))
    )
    (comp (ref "J9")
      (value "901200130")
      (footprint "CON_901200130_MOL")
      (description "No Description Available")
      (fields (field (name "COPYRIGHT") "Copyright (C) 2022 Ultra Librarian. All rights reserved."))
      (libsource (lib "901200130") (part "901200130"))
    )
    (comp (ref "J10")
      (value "CES-130-01-T-S")
      (footprint "CON30_1X30_TU_SLW_SAI")
      (description "No Description Available")
      (fields (field (name "COPYRIGHT") "Copyright (C) 2022 Ultra Librarian. All rights reserved."))
      (libsource (lib "CES-130-01-T-S") (part "CES-130-01-T-S"))
    )
    (comp (ref "J11")
      (value "SLW-120-01-G-S")
      (footprint "CON20_1X20_TU_SLW_SAI")
      (description "No Description Available")
      (fields (field (name "COPYRIGHT") "Copyright (C) 2022 Ultra Librarian. All rights reserved."))
      (libsource (lib "SLW-120-01-G-S") (part "SLW-120-01-G-S"))
    )
    (comp (ref "J12")
      (value "SLW-120-01-G-S")
      (footprint "CON20_1X20_TU_SLW_SAI")
      (description "No Description Available")
      (fields (field (name "COPYRIGHT") "Copyright (C) 2022 Ultra Librarian. All rights reserved."))
      (libsource (lib "SLW-120-01-G-S") (part "SLW-120-01-G-S"))
    )
    (comp (ref "J13")
      (value "CES-130-01-T-S")
      (footprint "CON30_1X30_TU_SLW_SAI")
      (description "No Description Available")
      (fields (field (name "COPYRIGHT") "Copyright (C) 2022 Ultra Librarian. All rights reserved."))
      (libsource (lib "CES-130-01-T-S") (part "CES-130-01-T-S"))
    )
    (comp (ref "J14")
      (value "T821112A1S100CEU")
      (footprint "CONN_T821112A1S100CEU_AMP")
      (description "No Description Available")
      (fields (field (name "COPYRIGHT") "Copyright (C) 2022 Ultra Librarian. All rights reserved."))
      (libsource (lib "T821112A1S100CEU") (part "T821112A1S100CEU"))
    )
    (comp (ref "J15")
      (value "22284110")
      (footprint "22-28-4110_MOL")
      (description "No Description Available")
      (fields (field (name "COPYRIGHT") "Copyright (C) 2022 Ultra Librarian. All rights reserved."))
      (libsource (lib "22284110") (part "22284110"))
    )
    (comp (ref "J16")
      (value "22284110")
      (footprint "22-28-4110_MOL")
      (description "No Description Available")
      (fields (field (name "COPYRIGHT") "Copyright (C) 2022 Ultra Librarian. All rights reserved."))
      (libsource (lib "22284110") (part "22284110"))
    )
    (comp (ref "J17")
      (value "825433-4")
      (footprint "CON4_1X4_P100UM_HDR2_TYC")
      (description "No Description Available")
      (fields (field (name "COPYRIGHT") "Copyright (C) 2022 Ultra Librarian. All rights reserved."))
      (libsource (lib "825433-4") (part "825433-4"))
    )
    (comp (ref "L1")
      (value "1mH")
      (footprint "MCSDRB7032-102MHF")
      (description "1mH 150mA inductor")
      (libsource (lib "MB - Misc") (part "MCSDRB7032-102MHF"))
    )
    (comp (ref "LED1")
      (value "Red")
      (footprint "LED-0603-RED")
      (description "LED 0603 SMD Hyper Red 630nm 220mcd 20mA")
      (libsource (lib "PBL - Light Sources") (part "LED_SMD_Red_0603_220mcd"))
    )
    (comp (ref "R1")
      (value "10K")
      (footprint "RESC1608N")
      (description "Resistor SMD chip 10k Ohm 0.1W 1% 0603")
      (fields (field (name "TOLERANCE") "±1%") (field (name "Comment") "Thick Film"))
      (libsource (lib "analogboard_v2") (part "RES_10K_0603_1%"))
    )
    (comp (ref "R2")
      (value "866R")
      (footprint "RESC1608N")
      (description "Resistor SMD chip 866 Ohm 0.1W 1% 0603")
      (fields (field (name "TOLERANCE") "±1%") (field (name "Comment") "Thick Film"))
      (libsource (lib "MB - Misc") (part "RES_866R_0603_1%_1"))
    )
    (comp (ref "R3")
      (value "RES 3.32k")
      (footprint "RC0603N_YAG")
      (description "No Description Available")
      (fields
        (field (name "MANUFACTURER_PART_NUMBER") "RC0603FR-073K32L")
        (field (name "COPYRIGHT") "Copyright (C) 2022 Ultra Librarian. All rights reserved.")
      )
      (libsource (lib "RC0603FR-073K32L") (part "RC0603FR-073K32L"))
    )
    (comp (ref "R4")
      (value "RES 3.32k")
      (footprint "RC0603N_YAG")
      (description "No Description Available")
      (fields
        (field (name "MANUFACTURER_PART_NUMBER") "RC0603FR-073K32L")
        (field (name "COPYRIGHT") "Copyright (C) 2022 Ultra Librarian. All rights reserved.")
      )
      (libsource (lib "RC0603FR-073K32L") (part "RC0603FR-073K32L"))
    )
    (comp (ref "R5")
      (value "RES 3.32k")
      (footprint "RC0603N_YAG")
      (description "No Description Available")
      (fields
        (field (name "MANUFACTURER_PART_NUMBER") "RC0603FR-073K32L")
        (field (name "COPYRIGHT") "Copyright (C) 2022 Ultra Librarian. All rights reserved.")
      )
      (libsource (lib "RC0603FR-073K32L") (part "RC0603FR-073K32L"))
    )
    (comp (ref "R6")
      (value "RES 14k")
      (footprint "RC0603N_YAG")
      (description "No Description Available")
      (fields
        (field (name "MANUFACTURER_PART_NUMBER") "RC0603FR-0714KL")
        (field (name "COPYRIGHT") "Copyright (C) 2022 Ultra Librarian. All rights reserved.")
      )
      (libsource (lib "RC0603FR-0714KL") (part "RC0603FR-0714KL"))
    )
    (comp (ref "R7")
      (value "10K")
      (footprint "RESC1608N")
      (description "Resistor SMD chip 10k Ohm 0.1W 1% 0603")
      (fields (field (name "TOLERANCE") "±1%") (field (name "Comment") "Thick Film"))
      (libsource (lib "analogboard_v2") (part "RES_10K_0603_1%"))
    )
    (comp (ref "R8")
      (value "10K")
      (footprint "RESC1608N")
      (description "Resistor SMD chip 10k Ohm 0.1W 1% 0603")
      (fields (field (name "TOLERANCE") "±1%") (field (name "Comment") "Thick Film"))
      (libsource (lib "analogboard_v2") (part "RES_10K_0603_1%"))
    )
    (comp (ref "R9")
      (value "10K")
      (footprint "RESC1608N")
      (description "Resistor SMD chip 10k Ohm 0.1W 1% 0603")
      (fields (field (name "TOLERANCE") "±1%") (field (name "Comment") "Thick Film"))
      (libsource (lib "analogboard_v2") (part "RES_10K_0603_1%"))
    )
    (comp (ref "R10")
      (value "10K")
      (footprint "RESC1608N")
      (description "Resistor SMD chip 10k Ohm 0.1W 1% 0603")
      (fields (field (name "TOLERANCE") "±1%") (field (name "Comment") "Thick Film"))
      (libsource (lib "analogboard_v2") (part "RES_10K_0603_1%"))
    )
    (comp (ref "R11")
      (value "2K21")
      (footprint "RESC1608N")
      (description "Resistor SMD chip 2.21k Ohm 0.1W 1% 0603")
      (fields (field (name "TOLERANCE") "±1%") (field (name "Comment") "Thick Film"))
      (libsource (lib "analogboard_v2") (part "RES_2K21_0603_1%"))
    )
    (comp (ref "R12")
      (value "2K21")
      (footprint "RESC1608N")
      (description "Resistor SMD chip 2.21k Ohm 0.1W 1% 0603")
      (fields (field (name "TOLERANCE") "±1%") (field (name "Comment") "Thick Film"))
      (libsource (lib "analogboard_v2") (part "RES_2K21_0603_1%"))
    )
    (comp (ref "R13")
      (value "2K21")
      (footprint "RESC1608N")
      (description "Resistor SMD chip 2.21k Ohm 0.1W 1% 0603")
      (fields (field (name "TOLERANCE") "±1%") (field (name "Comment") "Thick Film"))
      (libsource (lib "analogboard_v2") (part "RES_2K21_0603_1%"))
    )
    (comp (ref "R14")
      (value "2K21")
      (footprint "RESC1608N")
      (description "Resistor SMD chip 2.21k Ohm 0.1W 1% 0603")
      (fields (field (name "TOLERANCE") "±1%") (field (name "Comment") "Thick Film"))
      (libsource (lib "analogboard_v2") (part "RES_2K21_0603_1%"))
    )
    (comp (ref "R15")
      (value "2K21")
      (footprint "RESC1608N")
      (description "Resistor SMD chip 2.21k Ohm 0.1W 1% 0603")
      (fields (field (name "TOLERANCE") "±1%") (field (name "Comment") "Thick Film"))
      (libsource (lib "analogboard_v2") (part "RES_2K21_0603_1%"))
    )
    (comp (ref "R16")
      (value "2K21")
      (footprint "RESC1608N")
      (description "Resistor SMD chip 2.21k Ohm 0.1W 1% 0603")
      (fields (field (name "TOLERANCE") "±1%") (field (name "Comment") "Thick Film"))
      (libsource (lib "analogboard_v2") (part "RES_2K21_0603_1%"))
    )
    (comp (ref "R17")
      (value "RES50G")
      (footprint "RES_RH732A_TYC")
      (description "No Description Available")
      (fields
        (field (name "MANUFACTURER_PART_NUMBER") "RH73X2A50GNTN")
        (field (name "COPYRIGHT") "Copyright (C) 2022 Ultra Librarian. All rights reserved.")
      )
      (libsource (lib "RH73X2A50GNTN") (part "RH73X2A50GNTN"))
    )
    (comp (ref "R18")
      (value "RES 4.12 Mohm")
      (footprint "RC0805N_VIS")
      (description "No Description Available")
      (fields
        (field (name "MANUFACTURER_PART_NUMBER") "CRCW08054M12FKEA")
        (field (name "COPYRIGHT") "Copyright (C) 2022 Ultra Librarian. All rights reserved.")
      )
      (libsource (lib "CRCW08054M12FKEA") (part "CRCW08054M12FKEA"))
    )
    (comp (ref "R19")
      (value "RES100")
      (footprint "RC0603N_YAG")
      (description "No Description Available")
      (fields
        (field (name "MANUFACTURER_PART_NUMBER") "RC0603JR-07100RL")
        (field (name "COPYRIGHT") "Copyright (C) 2022 Ultra Librarian. All rights reserved.")
      )
      (libsource (lib "RC0603JR-07100RL") (part "RC0603JR-07100RL"))
    )
    (comp (ref "R20")
      (value "100K")
      (footprint "RESC1608N")
      (description "Resistor SMD chip 100k Ohm 0.1W 1% 0603")
      (fields (field (name "TOLERANCE") "±1%") (field (name "Comment") "Thick Film"))
      (libsource (lib "analogboard_v2") (part "RES_100K_0603_1%"))
    )
    (comp (ref "R21")
      (value "100K")
      (footprint "RESC1608N")
      (description "Resistor SMD chip 100k Ohm 0.1W 1% 0603")
      (fields (field (name "TOLERANCE") "±1%") (field (name "Comment") "Thick Film"))
      (libsource (lib "analogboard_v2") (part "RES_100K_0603_1%"))
    )
    (comp (ref "S1")
      (value "SWITCH_JS202011CQN_DPDT")
      (footprint "PCBComponent_1")
      (libsource (lib "dpdt_switch") (part "SWITCH_JS202011CQN_DPDT"))
    )
    (comp (ref "S2")
      (value "SWITCH_JS202011CQN_DPDT")
      (footprint "PCBComponent_1")
      (libsource (lib "dpdt_switch") (part "SWITCH_JS202011CQN_DPDT"))
    )
    (comp (ref "S3")
      (value "SWITCH_JS202011CQN_DPDT")
      (footprint "PCBComponent_1")
      (libsource (lib "dpdt_switch") (part "SWITCH_JS202011CQN_DPDT"))
    )
    (comp (ref "S4")
      (value "SWITCH_JS202011CQN_DPDT")
      (footprint "PCBComponent_1")
      (libsource (lib "dpdt_switch") (part "SWITCH_JS202011CQN_DPDT"))
    )
    (comp (ref "U1")
      (value "LP3961ES-2.5")
      (footprint "TS5B_TEX")
      (description "No Description Available")
      (fields (field (name "COPYRIGHT") "Copyright (C) 2022 Ultra Librarian. All rights reserved."))
      (libsource (lib "LP3961ES-2P5") (part "LP3961ES-2.5"))
    )
    (comp (ref "U2")
      (value "BD00C0AWHFP-CTR")
      (footprint "HRP5_BD00C0_ROM")
      (description "No Description Available")
      (fields (field (name "COPYRIGHT") "Copyright (C) 2022 Ultra Librarian. All rights reserved."))
      (libsource (lib "BD00C0AWHFP-CTR") (part "BD00C0AWHFP-CTR"))
    )
    (comp (ref "U3")
      (value "BD00C0AWHFP-CTR")
      (footprint "HRP5_BD00C0_ROM")
      (description "No Description Available")
      (fields (field (name "COPYRIGHT") "Copyright (C) 2022 Ultra Librarian. All rights reserved."))
      (libsource (lib "BD00C0AWHFP-CTR") (part "BD00C0AWHFP-CTR"))
    )
    (comp (ref "U4")
      (value "BD00C0AWHFP-CTR")
      (footprint "HRP5_BD00C0_ROM")
      (description "No Description Available")
      (fields (field (name "COPYRIGHT") "Copyright (C) 2022 Ultra Librarian. All rights reserved."))
      (libsource (lib "BD00C0AWHFP-CTR") (part "BD00C0AWHFP-CTR"))
    )
    (comp (ref "U5")
      (value "BD00C0AWHFP-CTR")
      (footprint "HRP5_BD00C0_ROM")
      (description "No Description Available")
      (fields (field (name "COPYRIGHT") "Copyright (C) 2022 Ultra Librarian. All rights reserved."))
      (libsource (lib "BD00C0AWHFP-CTR") (part "BD00C0AWHFP-CTR"))
    )
    (comp (ref "U6")
      (value "REF5025AIDG4")
      (footprint "D8")
      (description "No Description Available")
      (fields (field (name "COPYRIGHT") "Copyright (C) 2021 Ultra Librarian. All rights reserved."))
      (libsource (lib "REF5025AIDG4") (part "REF5025AIDG4"))
    )
    (comp (ref "U7")
      (value "DAC7614EB")
      (footprint "DB20")
      (description "No Description Available")
      (fields (field (name "COPYRIGHT") "Copyright (C) 2022 Ultra Librarian. All rights reserved."))
      (libsource (lib "DAC7614EB") (part "DAC7614EB"))
    )
    (comp (ref "U8")
      (value "DAC7614EB")
      (footprint "DB20")
      (description "No Description Available")
      (fields (field (name "COPYRIGHT") "Copyright (C) 2022 Ultra Librarian. All rights reserved."))
      (libsource (lib "DAC7614EB") (part "DAC7614EB"))
    )
    (comp (ref "U9")
      (value "TLV2771CDBVR")
      (footprint "DBV5")
      (description "No Description Available")
      (fields (field (name "COPYRIGHT") "Copyright (C) 2022 Ultra Librarian. All rights reserved."))
      (libsource (lib "TLV2771CDBVR") (part "TLV2771CDBVR"))
    )
    (comp (ref "U10")
      (value "BC817W")
      (footprint "SOT323_NEX")
      (description "No Description Available")
      (fields (field (name "COPYRIGHT") "Copyright (C) 2022 Ultra Librarian. All rights reserved."))
      (libsource (lib "BC817W") (part "BC817W"))
    )
    (comp (ref "U11")
      (value "TLV2771CDBVR")
      (footprint "DBV5")
      (description "No Description Available")
      (fields (field (name "COPYRIGHT") "Copyright (C) 2022 Ultra Librarian. All rights reserved."))
      (libsource (lib "TLV2771CDBVR") (part "TLV2771CDBVR"))
    )
    (comp (ref "U12")
      (value "BC817W")
      (footprint "SOT323_NEX")
      (description "No Description Available")
      (fields (field (name "COPYRIGHT") "Copyright (C) 2022 Ultra Librarian. All rights reserved."))
      (libsource (lib "BC817W") (part "BC817W"))
    )
    (comp (ref "U13")
      (value "TLV2771CDBVR")
      (footprint "DBV5")
      (description "No Description Available")
      (fields (field (name "COPYRIGHT") "Copyright (C) 2022 Ultra Librarian. All rights reserved."))
      (libsource (lib "TLV2771CDBVR") (part "TLV2771CDBVR"))
    )
    (comp (ref "U14")
      (value "BC817W")
      (footprint "SOT323_NEX")
      (description "No Description Available")
      (fields (field (name "COPYRIGHT") "Copyright (C) 2022 Ultra Librarian. All rights reserved."))
      (libsource (lib "BC817W") (part "BC817W"))
    )
    (comp (ref "U15")
      (value "DAC7614EB")
      (footprint "DB20")
      (description "No Description Available")
      (fields (field (name "COPYRIGHT") "Copyright (C) 2022 Ultra Librarian. All rights reserved."))
      (libsource (lib "DAC7614EB") (part "DAC7614EB"))
    )
    (comp (ref "U16")
      (value "TLV2771CDBVR")
      (footprint "DBV5")
      (description "No Description Available")
      (fields (field (name "COPYRIGHT") "Copyright (C) 2022 Ultra Librarian. All rights reserved."))
      (libsource (lib "TLV2771CDBVR") (part "TLV2771CDBVR"))
    )
    (comp (ref "U17")
      (value "BC817W")
      (footprint "SOT323_NEX")
      (description "No Description Available")
      (fields (field (name "COPYRIGHT") "Copyright (C) 2022 Ultra Librarian. All rights reserved."))
      (libsource (lib "BC817W") (part "BC817W"))
    )
    (comp (ref "U18")
      (value "TLV2771CDBVR")
      (footprint "DBV5")
      (description "No Description Available")
      (fields (field (name "COPYRIGHT") "Copyright (C) 2022 Ultra Librarian. All rights reserved."))
      (libsource (lib "TLV2771CDBVR") (part "TLV2771CDBVR"))
    )
    (comp (ref "U19")
      (value "BC817W")
      (footprint "SOT323_NEX")
      (description "No Description Available")
      (fields (field (name "COPYRIGHT") "Copyright (C) 2022 Ultra Librarian. All rights reserved."))
      (libsource (lib "BC817W") (part "BC817W"))
    )
    (comp (ref "U20")
      (value "TLV2771CDBVR")
      (footprint "DBV5")
      (description "No Description Available")
      (fields (field (name "COPYRIGHT") "Copyright (C) 2022 Ultra Librarian. All rights reserved."))
      (libsource (lib "TLV2771CDBVR") (part "TLV2771CDBVR"))
    )
    (comp (ref "U21")
      (value "BC817W")
      (footprint "SOT323_NEX")
      (description "No Description Available")
      (fields (field (name "COPYRIGHT") "Copyright (C) 2022 Ultra Librarian. All rights reserved."))
      (libsource (lib "BC817W") (part "BC817W"))
    )
    (comp (ref "U22")
      (value "ADS8344E")
      (footprint "DBQ20")
      (description "No Description Available")
      (fields (field (name "COPYRIGHT") "Copyright (C) 2022 Ultra Librarian. All rights reserved."))
      (libsource (lib "ADS8344E") (part "ADS8344E"))
    )
    (comp (ref "U23")
      (value "REF5025AIDG4")
      (footprint "D8")
      (description "No Description Available")
      (fields (field (name "COPYRIGHT") "Copyright (C) 2021 Ultra Librarian. All rights reserved."))
      (libsource (lib "REF5025AIDG4") (part "REF5025AIDG4"))
    )
    (comp (ref "U24")
      (value "TLV2771CDBVR")
      (footprint "DBV5")
      (description "No Description Available")
      (fields (field (name "COPYRIGHT") "Copyright (C) 2022 Ultra Librarian. All rights reserved."))
      (libsource (lib "TLV2771CDBVR") (part "TLV2771CDBVR"))
    )
    (comp (ref "U25")
      (value "OPA380AIDGKT")
      (footprint "DGK8")
      (description "No Description Available")
      (fields (field (name "COPYRIGHT") "Copyright (C) 2022 Ultra Librarian. All rights reserved."))
      (libsource (lib "OPA380AIDGKT") (part "OPA380AIDGKT"))
    )
  )
  (nets
    (net (code "1") (name "/ACK") (class "Default")
      (node (ref "J12") (pin "9") (pinfunction "9_9") (pintype "passive"))
      (node (ref "J14") (pin "7") (pinfunction "7_7") (pintype "passive"))
    )
    (net (code "2") (name "/ACKX_PULSE_EXT<0>") (class "Default")
      (node (ref "J10") (pin "12") (pinfunction "12_12") (pintype "passive"))
      (node (ref "J10") (pin "15") (pinfunction "15_15") (pintype "passive"))
      (node (ref "J10") (pin "18") (pinfunction "18_18") (pintype "passive"))
      (node (ref "J10") (pin "21") (pinfunction "21_21") (pintype "passive"))
      (node (ref "J10") (pin "24") (pinfunction "24_24") (pintype "passive"))
      (node (ref "J10") (pin "27") (pinfunction "27_27") (pintype "passive"))
      (node (ref "J10") (pin "3") (pinfunction "3_3") (pintype "passive"))
      (node (ref "J10") (pin "30") (pinfunction "30_30") (pintype "passive"))
      (node (ref "J10") (pin "6") (pinfunction "6_6") (pintype "passive"))
      (node (ref "J10") (pin "9") (pinfunction "9_9") (pintype "passive"))
      (node (ref "J9") (pin "1") (pinfunction "1_1") (pintype "passive"))
    )
    (net (code "3") (name "/ACKX_PULSE_EXT<1>") (class "Default")
      (node (ref "J9") (pin "2") (pinfunction "2_2") (pintype "passive"))
    )
    (net (code "4") (name "/ACKX_PULSE_EXT<2>") (class "Default")
      (node (ref "J9") (pin "3") (pinfunction "3_3") (pintype "passive"))
    )
    (net (code "5") (name "/ACKX_PULSE_EXT<3>") (class "Default")
      (node (ref "J9") (pin "4") (pinfunction "4_4") (pintype "passive"))
    )
    (net (code "6") (name "/ACKX_PULSE_EXT<4>") (class "Default")
      (node (ref "J9") (pin "5") (pinfunction "5_5") (pintype "passive"))
    )
    (net (code "7") (name "/ACKX_PULSE_EXT<5>") (class "Default")
      (node (ref "J9") (pin "6") (pinfunction "6_6") (pintype "passive"))
    )
    (net (code "8") (name "/ACKX_PULSE_EXT<6>") (class "Default")
      (node (ref "J9") (pin "7") (pinfunction "7_7") (pintype "passive"))
    )
    (net (code "9") (name "/ACKX_PULSE_EXT<7>") (class "Default")
      (node (ref "J9") (pin "8") (pinfunction "8_8") (pintype "passive"))
    )
    (net (code "10") (name "/ACKX_PULSE_EXT<8>") (class "Default")
      (node (ref "J9") (pin "9") (pinfunction "9_9") (pintype "passive"))
    )
    (net (code "11") (name "/ACKX_PULSE_EXT<9>") (class "Default")
      (node (ref "J9") (pin "10") (pinfunction "10_10") (pintype "passive"))
    )
    (net (code "12") (name "/ADDRX<0>") (class "Default")
      (node (ref "J12") (pin "6") (pinfunction "6_6") (pintype "passive"))
      (node (ref "J14") (pin "4") (pinfunction "4_4") (pintype "passive"))
    )
    (net (code "13") (name "/ADDRX<1>") (class "Default")
      (node (ref "J12") (pin "5") (pinfunction "5_5") (pintype "passive"))
      (node (ref "J14") (pin "3") (pinfunction "3_3") (pintype "passive"))
    )
    (net (code "14") (name "/ADDRX<2>") (class "Default")
      (node (ref "J12") (pin "4") (pinfunction "4_4") (pintype "passive"))
      (node (ref "J14") (pin "2") (pinfunction "2_2") (pintype "passive"))
    )
    (net (code "15") (name "/ADDRX<3>") (class "Default")
      (node (ref "J12") (pin "3") (pinfunction "3_3") (pintype "passive"))
      (node (ref "J14") (pin "1") (pinfunction "1_1") (pintype "passive"))
    )
    (net (code "16") (name "/ADDRY<0>") (class "Default")
      (node (ref "J12") (pin "14") (pinfunction "14_14") (pintype "passive"))
      (node (ref "J14") (pin "12") (pinfunction "12_12") (pintype "passive"))
    )
    (net (code "17") (name "/ADDRY<1>") (class "Default")
      (node (ref "J12") (pin "13") (pinfunction "13_13") (pintype "passive"))
      (node (ref "J14") (pin "11") (pinfunction "11_11") (pintype "passive"))
    )
    (net (code "18") (name "/ADDRY<2>") (class "Default")
      (node (ref "J12") (pin "12") (pinfunction "12_12") (pintype "passive"))
      (node (ref "J14") (pin "10") (pinfunction "10_10") (pintype "passive"))
    )
    (net (code "19") (name "/ADDRY<3>") (class "Default")
      (node (ref "J12") (pin "11") (pinfunction "11_11") (pintype "passive"))
      (node (ref "J14") (pin "9") (pinfunction "9_9") (pintype "passive"))
    )
    (net (code "20") (name "/AER_DIS_EXT") (class "Default")
      (node (ref "J13") (pin "23") (pinfunction "23_23") (pintype "passive"))
      (node (ref "S4") (pin "5") (pinfunction "5_5") (pintype "passive"))
    )
    (net (code "21") (name "/AER_RST") (class "Default")
      (node (ref "J12") (pin "10") (pinfunction "10_10") (pintype "passive"))
      (node (ref "J14") (pin "8") (pinfunction "8_8") (pintype "passive"))
    )
    (net (code "22") (name "/AGND") (class "Default")
      (node (ref "J11") (pin "9") (pinfunction "9_9") (pintype "passive"))
    )
    (net (code "24") (name "/BUSY") (class "Default")
      (node (ref "U22") (pin "16") (pinfunction "BUSY_16") (pintype "output"))
    )
    (net (code "25") (name "/CLK") (class "Default")
      (node (ref "U15") (pin "13") (pinfunction "CLK_13") (pintype "passive"))
      (node (ref "U22") (pin "19") (pinfunction "DCLK_19") (pintype "input"))
      (node (ref "U7") (pin "13") (pinfunction "CLK_13") (pintype "passive"))
      (node (ref "U8") (pin "13") (pinfunction "CLK_13") (pintype "passive"))
    )
    (net (code "26") (name "/CSb_ADC") (class "Default")
      (node (ref "U22") (pin "18") (pinfunction "*CS_18") (pintype "input"))
    )
    (net (code "27") (name "/CSb_IDAC") (class "Default")
      (node (ref "U15") (pin "14") (pinfunction "*CS_14") (pintype "input"))
    )
    (net (code "28") (name "/CSb_IDAC_scaled") (class "Default")
      (node (ref "U8") (pin "14") (pinfunction "*CS_14") (pintype "input"))
    )
    (net (code "29") (name "/CSb_VDAC") (class "Default")
      (node (ref "U7") (pin "14") (pinfunction "*CS_14") (pintype "input"))
    )
    (net (code "30") (name "/DGND") (class "Default")
      (node (ref "J12") (pin "2") (pinfunction "2_2") (pintype "passive"))
    )
    (net (code "31") (name "/DVDD_EXT") (class "Default")
      (node (ref "S1") (pin "5") (pinfunction "5_5") (pintype "passive"))
    )
    (net (code "32") (name "/HEM_OUT") (class "Default")
      (node (ref "C69") (pin "1") (pinfunction "1_1") (pintype "passive"))
      (node (ref "J11") (pin "8") (pinfunction "8_8") (pintype "passive"))
      (node (ref "R18") (pin "2") (pinfunction "2_2") (pintype "passive"))
      (node (ref "U25") (pin "2") (pinfunction "IN-_2") (pintype "input"))
    )
    (net (code "33") (name "/HEM_OUT_I2V") (class "Default")
      (node (ref "C69") (pin "2") (pinfunction "2_2") (pintype "passive"))
      (node (ref "R18") (pin "1") (pinfunction "1_1") (pintype "passive"))
      (node (ref "U22") (pin "1") (pinfunction "CH0_1") (pintype "input"))
      (node (ref "U25") (pin "6") (pinfunction "OUT_6") (pintype "output"))
    )
    (net (code "34") (name "/IBLEED") (class "Default")
      (node (ref "J11") (pin "16") (pinfunction "16_16") (pintype "passive"))
      (node (ref "U10") (pin "3") (pinfunction "COLLECTOR_3") (pintype "passive"))
    )
    (net (code "35") (name "/ISLEW") (class "Default")
      (node (ref "J11") (pin "18") (pinfunction "18_18") (pintype "passive"))
      (node (ref "U17") (pin "3") (pinfunction "COLLECTOR_3") (pintype "passive"))
    )
    (net (code "36") (name "/ISPK") (class "Default")
      (node (ref "J11") (pin "17") (pinfunction "17_17") (pintype "passive"))
      (node (ref "U19") (pin "3") (pinfunction "COLLECTOR_3") (pintype "passive"))
    )
    (net (code "37") (name "/ISPKFAST") (class "Default")
      (node (ref "J11") (pin "13") (pinfunction "13_13") (pintype "passive"))
      (node (ref "U21") (pin "3") (pinfunction "COLLECTOR_3") (pintype "passive"))
    )
    (net (code "38") (name "/ITAIL") (class "Default")
      (node (ref "J11") (pin "14") (pinfunction "14_14") (pintype "passive"))
      (node (ref "U14") (pin "3") (pinfunction "COLLECTOR_3") (pintype "passive"))
    )
    (net (code "39") (name "/ITH") (class "Default")
      (node (ref "J11") (pin "15") (pinfunction "15_15") (pintype "passive"))
      (node (ref "U12") (pin "3") (pinfunction "COLLECTOR_3") (pintype "passive"))
    )
    (net (code "40") (name "/LCVDD_EXT") (class "Default")
      (node (ref "S2") (pin "5") (pinfunction "5_5") (pintype "passive"))
    )
    (net (code "41") (name "/LDACb") (class "Default")
      (node (ref "U15") (pin "18") (pinfunction "*LOADDACS_18") (pintype "passive"))
      (node (ref "U7") (pin "18") (pinfunction "*LOADDACS_18") (pintype "passive"))
      (node (ref "U8") (pin "18") (pinfunction "*LOADDACS_18") (pintype "passive"))
    )
    (net (code "42") (name "/N_COX_OFF_EXT<0>") (class "Default")
      (node (ref "J10") (pin "11") (pinfunction "11_11") (pintype "passive"))
      (node (ref "J10") (pin "14") (pinfunction "14_14") (pintype "passive"))
      (node (ref "J10") (pin "17") (pinfunction "17_17") (pintype "passive"))
      (node (ref "J10") (pin "2") (pinfunction "2_2") (pintype "passive"))
      (node (ref "J10") (pin "20") (pinfunction "20_20") (pintype "passive"))
      (node (ref "J10") (pin "23") (pinfunction "23_23") (pintype "passive"))
      (node (ref "J10") (pin "26") (pinfunction "26_26") (pintype "passive"))
      (node (ref "J10") (pin "29") (pinfunction "29_29") (pintype "passive"))
      (node (ref "J10") (pin "5") (pinfunction "5_5") (pintype "passive"))
      (node (ref "J10") (pin "8") (pinfunction "8_8") (pintype "passive"))
      (node (ref "J8") (pin "1") (pinfunction "1_1") (pintype "passive"))
    )
    (net (code "43") (name "/N_COX_OFF_EXT<1>") (class "Default")
      (node (ref "J8") (pin "2") (pinfunction "2_2") (pintype "passive"))
    )
    (net (code "44") (name "/N_COX_OFF_EXT<2>") (class "Default")
      (node (ref "J8") (pin "3") (pinfunction "3_3") (pintype "passive"))
    )
    (net (code "45") (name "/N_COX_OFF_EXT<3>") (class "Default")
      (node (ref "J8") (pin "4") (pinfunction "4_4") (pintype "passive"))
    )
    (net (code "46") (name "/N_COX_OFF_EXT<4>") (class "Default")
      (node (ref "J8") (pin "5") (pinfunction "5_5") (pintype "passive"))
    )
    (net (code "47") (name "/N_COX_OFF_EXT<5>") (class "Default")
      (node (ref "J8") (pin "6") (pinfunction "6_6") (pintype "passive"))
    )
    (net (code "48") (name "/N_COX_OFF_EXT<6>") (class "Default")
      (node (ref "J8") (pin "7") (pinfunction "7_7") (pintype "passive"))
    )
    (net (code "49") (name "/N_COX_OFF_EXT<7>") (class "Default")
      (node (ref "J8") (pin "8") (pinfunction "8_8") (pintype "passive"))
    )
    (net (code "50") (name "/N_COX_OFF_EXT<8>") (class "Default")
      (node (ref "J8") (pin "9") (pinfunction "9_9") (pintype "passive"))
    )
    (net (code "51") (name "/N_COX_OFF_EXT<9>") (class "Default")
      (node (ref "J8") (pin "10") (pinfunction "10_10") (pintype "passive"))
    )
    (net (code "52") (name "/N_COX_ON_EXT<0>") (class "Default")
      (node (ref "J10") (pin "1") (pinfunction "1_1") (pintype "passive"))
      (node (ref "J10") (pin "10") (pinfunction "10_10") (pintype "passive"))
      (node (ref "J10") (pin "13") (pinfunction "13_13") (pintype "passive"))
      (node (ref "J10") (pin "16") (pinfunction "16_16") (pintype "passive"))
      (node (ref "J10") (pin "19") (pinfunction "19_19") (pintype "passive"))
      (node (ref "J10") (pin "22") (pinfunction "22_22") (pintype "passive"))
      (node (ref "J10") (pin "25") (pinfunction "25_25") (pintype "passive"))
      (node (ref "J10") (pin "28") (pinfunction "28_28") (pintype "passive"))
      (node (ref "J10") (pin "4") (pinfunction "4_4") (pintype "passive"))
      (node (ref "J10") (pin "7") (pinfunction "7_7") (pintype "passive"))
      (node (ref "J7") (pin "1") (pinfunction "1_1") (pintype "passive"))
    )
    (net (code "53") (name "/N_COX_ON_EXT<1>") (class "Default")
      (node (ref "J7") (pin "2") (pinfunction "2_2") (pintype "passive"))
    )
    (net (code "54") (name "/N_COX_ON_EXT<2>") (class "Default")
      (node (ref "J7") (pin "3") (pinfunction "3_3") (pintype "passive"))
    )
    (net (code "55") (name "/N_COX_ON_EXT<3>") (class "Default")
      (node (ref "J7") (pin "4") (pinfunction "4_4") (pintype "passive"))
    )
    (net (code "56") (name "/N_COX_ON_EXT<4>") (class "Default")
      (node (ref "J7") (pin "5") (pinfunction "5_5") (pintype "passive"))
    )
    (net (code "57") (name "/N_COX_ON_EXT<5>") (class "Default")
      (node (ref "J7") (pin "6") (pinfunction "6_6") (pintype "passive"))
    )
    (net (code "58") (name "/N_COX_ON_EXT<6>") (class "Default")
      (node (ref "J7") (pin "7") (pinfunction "7_7") (pintype "passive"))
    )
    (net (code "59") (name "/N_COX_ON_EXT<7>") (class "Default")
      (node (ref "J7") (pin "8") (pinfunction "8_8") (pintype "passive"))
    )
    (net (code "60") (name "/N_COX_ON_EXT<8>") (class "Default")
      (node (ref "J7") (pin "9") (pinfunction "9_9") (pintype "passive"))
    )
    (net (code "61") (name "/N_COX_ON_EXT<9>") (class "Default")
      (node (ref "J7") (pin "10") (pinfunction "10_10") (pintype "passive"))
    )
    (net (code "62") (name "/N_P_EXT<0>") (class "Default")
      (node (ref "J13") (pin "22") (pinfunction "22_22") (pintype "passive"))
      (node (ref "J15") (pin "A1") (pinfunction "A1_A1") (pintype "passive"))
    )
    (net (code "63") (name "/N_P_EXT<1>") (class "Default")
      (node (ref "J13") (pin "20") (pinfunction "20_20") (pintype "passive"))
      (node (ref "J15") (pin "A2") (pinfunction "A2_A2") (pintype "passive"))
    )
    (net (code "64") (name "/N_P_EXT<2>") (class "Default")
      (node (ref "J13") (pin "18") (pinfunction "18_18") (pintype "passive"))
      (node (ref "J15") (pin "A3") (pinfunction "A3_A3") (pintype "passive"))
    )
    (net (code "65") (name "/N_P_EXT<3>") (class "Default")
      (node (ref "J13") (pin "16") (pinfunction "16_16") (pintype "passive"))
      (node (ref "J15") (pin "A4") (pinfunction "A4_A4") (pintype "passive"))
    )
    (net (code "66") (name "/N_P_EXT<4>") (class "Default")
      (node (ref "J13") (pin "14") (pinfunction "14_14") (pintype "passive"))
      (node (ref "J15") (pin "A5") (pinfunction "A5_A5") (pintype "passive"))
    )
    (net (code "67") (name "/N_P_EXT<5>") (class "Default")
      (node (ref "J13") (pin "12") (pinfunction "12_12") (pintype "passive"))
      (node (ref "J15") (pin "A6") (pinfunction "A6_A6") (pintype "passive"))
    )
    (net (code "68") (name "/N_P_EXT<6>") (class "Default")
      (node (ref "J13") (pin "10") (pinfunction "10_10") (pintype "passive"))
      (node (ref "J15") (pin "A7") (pinfunction "A7_A7") (pintype "passive"))
    )
    (net (code "69") (name "/N_P_EXT<7>") (class "Default")
      (node (ref "J13") (pin "8") (pinfunction "8_8") (pintype "passive"))
      (node (ref "J15") (pin "A8") (pinfunction "A8_A8") (pintype "passive"))
    )
    (net (code "70") (name "/N_P_EXT<8>") (class "Default")
      (node (ref "J13") (pin "6") (pinfunction "6_6") (pintype "passive"))
      (node (ref "J15") (pin "A9") (pinfunction "A9_A9") (pintype "passive"))
    )
    (net (code "71") (name "/N_P_EXT<9>") (class "Default")
      (node (ref "J13") (pin "4") (pinfunction "4_4") (pintype "passive"))
      (node (ref "J15") (pin "A10") (pinfunction "A10_A10") (pintype "passive"))
    )
    (net (code "72") (name "/N_P_EXT<10>") (class "Default")
      (node (ref "J13") (pin "2") (pinfunction "2_2") (pintype "passive"))
      (node (ref "J15") (pin "A11") (pinfunction "A11_A11") (pintype "passive"))
    )
    (net (code "73") (name "/POLING_MODE") (class "Default")
      (node (ref "J13") (pin "28") (pinfunction "28_28") (pintype "passive"))
    )
    (net (code "74") (name "/POS_CALIB") (class "Default")
      (node (ref "J13") (pin "27") (pinfunction "27_27") (pintype "passive"))
    )
    (net (code "75") (name "/POS_TEST") (class "Default")
      (node (ref "J13") (pin "26") (pinfunction "26_26") (pintype "passive"))
      (node (ref "R19") (pin "1") (pinfunction "1_1") (pintype "passive"))
    )
    (net (code "76") (name "/POS_TEST_CAMP") (class "Default")
      (node (ref "C72") (pin "1") (pinfunction "1_1") (pintype "passive"))
      (node (ref "R17") (pin "2") (pinfunction "2_2") (pintype "passive"))
      (node (ref "U22") (pin "2") (pinfunction "CH1_2") (pintype "input"))
      (node (ref "U24") (pin "1") (pinfunction "OUT_1") (pintype "output"))
    )
    (net (code "77") (name "/REQOFF") (class "Default")
      (node (ref "J12") (pin "8") (pinfunction "8_8") (pintype "passive"))
      (node (ref "J14") (pin "6") (pinfunction "6_6") (pintype "passive"))
    )
    (net (code "78") (name "/REQON") (class "Default")
      (node (ref "J12") (pin "7") (pinfunction "7_7") (pintype "passive"))
      (node (ref "J14") (pin "5") (pinfunction "5_5") (pintype "passive"))
    )
    (net (code "79") (name "/RESETb") (class "Default")
      (node (ref "U15") (pin "19") (pinfunction "*RESET_19") (pintype "input"))
      (node (ref "U7") (pin "19") (pinfunction "*RESET_19") (pintype "input"))
      (node (ref "U8") (pin "19") (pinfunction "*RESET_19") (pintype "input"))
    )
    (net (code "80") (name "/SCLK") (class "Default")
      (node (ref "J11") (pin "1") (pinfunction "1_1") (pintype "passive"))
      (node (ref "J17") (pin "2") (pinfunction "2_2") (pintype "passive"))
    )
    (net (code "81") (name "/SDI") (class "Default")
      (node (ref "U15") (pin "12") (pinfunction "SDI_12") (pintype "input"))
      (node (ref "U22") (pin "17") (pinfunction "DIN_17") (pintype "input"))
      (node (ref "U7") (pin "12") (pinfunction "SDI_12") (pintype "input"))
      (node (ref "U8") (pin "12") (pinfunction "SDI_12") (pintype "input"))
    )
    (net (code "82") (name "/SDOUT") (class "Default")
      (node (ref "U22") (pin "15") (pinfunction "DOUT_15") (pintype "output"))
    )
    (net (code "83") (name "/SHIFT") (class "Default")
      (node (ref "J11") (pin "2") (pinfunction "2_2") (pintype "passive"))
      (node (ref "J17") (pin "1") (pinfunction "1_1") (pintype "passive"))
    )
    (net (code "84") (name "/SIN") (class "Default")
      (node (ref "J12") (pin "20") (pinfunction "20_20") (pintype "passive"))
      (node (ref "J17") (pin "4") (pinfunction "4_4") (pintype "passive"))
    )
    (net (code "85") (name "/SOUT") (class "Default")
      (node (ref "J13") (pin "30") (pinfunction "30_30") (pintype "passive"))
      (node (ref "J17") (pin "3") (pinfunction "3_3") (pintype "passive"))
    )
    (net (code "86") (name "/S_EXT<0>") (class "Default")
      (node (ref "J13") (pin "21") (pinfunction "21_21") (pintype "passive"))
      (node (ref "J16") (pin "A1") (pinfunction "A1_A1") (pintype "passive"))
    )
    (net (code "87") (name "/S_EXT<1>") (class "Default")
      (node (ref "J13") (pin "19") (pinfunction "19_19") (pintype "passive"))
      (node (ref "J16") (pin "A2") (pinfunction "A2_A2") (pintype "passive"))
    )
    (net (code "88") (name "/S_EXT<2>") (class "Default")
      (node (ref "J13") (pin "17") (pinfunction "17_17") (pintype "passive"))
      (node (ref "J16") (pin "A3") (pinfunction "A3_A3") (pintype "passive"))
    )
    (net (code "89") (name "/S_EXT<3>") (class "Default")
      (node (ref "J13") (pin "15") (pinfunction "15_15") (pintype "passive"))
      (node (ref "J16") (pin "A4") (pinfunction "A4_A4") (pintype "passive"))
    )
    (net (code "90") (name "/S_EXT<4>") (class "Default")
      (node (ref "J13") (pin "13") (pinfunction "13_13") (pintype "passive"))
      (node (ref "J16") (pin "A5") (pinfunction "A5_A5") (pintype "passive"))
    )
    (net (code "91") (name "/S_EXT<5>") (class "Default")
      (node (ref "J13") (pin "11") (pinfunction "11_11") (pintype "passive"))
      (node (ref "J16") (pin "A6") (pinfunction "A6_A6") (pintype "passive"))
    )
    (net (code "92") (name "/S_EXT<6>") (class "Default")
      (node (ref "J13") (pin "9") (pinfunction "9_9") (pintype "passive"))
      (node (ref "J16") (pin "A7") (pinfunction "A7_A7") (pintype "passive"))
    )
    (net (code "93") (name "/S_EXT<7>") (class "Default")
      (node (ref "J13") (pin "7") (pinfunction "7_7") (pintype "passive"))
      (node (ref "J16") (pin "A8") (pinfunction "A8_A8") (pintype "passive"))
    )
    (net (code "94") (name "/S_EXT<8>") (class "Default")
      (node (ref "J13") (pin "5") (pinfunction "5_5") (pintype "passive"))
      (node (ref "J16") (pin "A9") (pinfunction "A9_A9") (pintype "passive"))
    )
    (net (code "95") (name "/S_EXT<9>") (class "Default")
      (node (ref "J13") (pin "3") (pinfunction "3_3") (pintype "passive"))
      (node (ref "J16") (pin "A10") (pinfunction "A10_A10") (pintype "passive"))
    )
    (net (code "96") (name "/S_EXT<10>") (class "Default")
      (node (ref "J13") (pin "1") (pinfunction "1_1") (pintype "passive"))
      (node (ref "J16") (pin "A11") (pinfunction "A11_A11") (pintype "passive"))
    )
    (net (code "97") (name "/TSENSE") (class "Default")
      (node (ref "J12") (pin "19") (pinfunction "19_19") (pintype "passive"))
      (node (ref "U22") (pin "3") (pinfunction "CH2_3") (pintype "input"))
    )
    (net (code "98") (name "/VBLEED") (class "Default")
      (node (ref "U8") (pin "9") (pinfunction "VOUTA_9") (pintype "output"))
      (node (ref "U9") (pin "3") (pinfunction "IN+_3") (pintype "input"))
    )
    (net (code "100") (name "/VIL") (class "Default")
      (node (ref "J11") (pin "19") (pinfunction "19_19") (pintype "passive"))
      (node (ref "U7") (pin "9") (pinfunction "VOUTA_9") (pintype "output"))
    )
    (net (code "101") (name "/VMODE_EXT") (class "Default")
      (node (ref "J13") (pin "24") (pinfunction "24_24") (pintype "passive"))
      (node (ref "S3") (pin "5") (pinfunction "5_5") (pintype "passive"))
    )
    (net (code "102") (name "/VPOS_AFE") (class "Default")
      (node (ref "J13") (pin "25") (pinfunction "25_25") (pintype "passive"))
    )
    (net (code "103") (name "/VPOS_CM") (class "Default")
      (node (ref "J11") (pin "12") (pinfunction "12_12") (pintype "passive"))
      (node (ref "U7") (pin "8") (pinfunction "VOUTB_8") (pintype "output"))
    )
    (net (code "104") (name "/VREFH") (class "Default")
      (node (ref "J11") (pin "11") (pinfunction "11_11") (pintype "passive"))
      (node (ref "U7") (pin "3") (pinfunction "VOUTC_3") (pintype "output"))
    )
    (net (code "105") (name "/VREFL") (class "Default")
      (node (ref "J11") (pin "10") (pinfunction "10_10") (pintype "passive"))
      (node (ref "U7") (pin "2") (pinfunction "VOUTD_2") (pintype "output"))
    )
    (net (code "106") (name "/VREF_2P5V") (class "Default")
      (node (ref "C17") (pin "1") (pintype "passive"))
      (node (ref "C23") (pin "1") (pintype "passive"))
      (node (ref "C55") (pin "1") (pintype "passive"))
      (node (ref "U15") (pin "7") (pinfunction "VREFH_7") (pintype "input"))
      (node (ref "U6") (pin "6") (pinfunction "VOUT_6") (pintype "output"))
      (node (ref "U7") (pin "7") (pinfunction "VREFH_7") (pintype "input"))
      (node (ref "U8") (pin "7") (pinfunction "VREFH_7") (pintype "input"))
    )
    (net (code "107") (name "/VREF_2P5V_ADC") (class "Default")
      (node (ref "C74") (pin "1") (pintype "passive"))
      (node (ref "C75") (pin "1") (pintype "passive"))
      (node (ref "U22") (pin "11") (pinfunction "VREF_11") (pintype "input"))
      (node (ref "U23") (pin "6") (pinfunction "VOUT_6") (pintype "output"))
      (node (ref "U25") (pin "3") (pinfunction "IN+_3") (pintype "input"))
    )
    (net (code "108") (name "/VSLEW") (class "Default")
      (node (ref "U15") (pin "9") (pinfunction "VOUTA_9") (pintype "output"))
      (node (ref "U16") (pin "3") (pinfunction "IN+_3") (pintype "input"))
    )
    (net (code "109") (name "/VSPK") (class "Default")
      (node (ref "U15") (pin "8") (pinfunction "VOUTB_8") (pintype "output"))
      (node (ref "U18") (pin "3") (pinfunction "IN+_3") (pintype "input"))
    )
    (net (code "110") (name "/VSPKFAST") (class "Default")
      (node (ref "U15") (pin "3") (pinfunction "VOUTC_3") (pintype "output"))
      (node (ref "U20") (pin "3") (pinfunction "IN+_3") (pintype "input"))
    )
    (net (code "111") (name "/VSS") (class "Default")
      (node (ref "J12") (pin "17") (pinfunction "17_17") (pintype "passive"))
    )
    (net (code "112") (name "/VSSPST") (class "Default")
      (node (ref "J12") (pin "16") (pinfunction "16_16") (pintype "passive"))
    )
    (net (code "113") (name "/VTAIL") (class "Default")
      (node (ref "U13") (pin "3") (pinfunction "IN+_3") (pintype "input"))
      (node (ref "U8") (pin "3") (pinfunction "VOUTC_3") (pintype "output"))
    )
    (net (code "114") (name "/VTH") (class "Default")
      (node (ref "U11") (pin "3") (pinfunction "IN+_3") (pintype "input"))
      (node (ref "U8") (pin "8") (pinfunction "VOUTB_8") (pintype "output"))
    )
    (net (code "115") (name "/VTOP") (class "Default")
      (node (ref "J13") (pin "29") (pinfunction "29_29") (pintype "passive"))
    )
    (net (code "116") (name "AVDD") (class "Default")
      (node (ref "C29") (pin "1") (pintype "passive"))
      (node (ref "C30") (pin "1") (pintype "passive"))
      (node (ref "C41") (pin "1") (pintype "passive"))
      (node (ref "C44") (pin "1") (pintype "passive"))
      (node (ref "C6") (pin "2") (pinfunction "2_2") (pintype "passive"))
      (node (ref "J11") (pin "20") (pinfunction "20_20") (pintype "passive"))
      (node (ref "J11") (pin "7") (pinfunction "7_7") (pintype "passive"))
      (node (ref "J4") (pin "1") (pinfunction "1_1") (pintype "passive"))
      (node (ref "R3") (pin "1") (pinfunction "1_1") (pintype "passive"))
      (node (ref "U2") (pin "4") (pinfunction "VO_4") (pintype "output"))
    )
    (net (code "117") (name "DVDD") (class "Default")
      (node (ref "C10") (pin "2") (pinfunction "2_2") (pintype "passive"))
      (node (ref "C27") (pin "1") (pintype "passive"))
      (node (ref "C28") (pin "1") (pintype "passive"))
      (node (ref "C50") (pin "1") (pintype "passive"))
      (node (ref "C52") (pin "1") (pintype "passive"))
      (node (ref "J11") (pin "3") (pinfunction "3_3") (pintype "passive"))
      (node (ref "J12") (pin "1") (pinfunction "1_1") (pintype "passive"))
      (node (ref "J5") (pin "1") (pinfunction "1_1") (pintype "passive"))
      (node (ref "R5") (pin "1") (pinfunction "1_1") (pintype "passive"))
      (node (ref "U4") (pin "4") (pinfunction "VO_4") (pintype "output"))
    )
    (net (code "118") (name "GND") (class "Default")
      (node (ref "C1") (pin "-") (pinfunction "-_-") (pintype "passive"))
      (node (ref "C10") (pin "1") (pinfunction "1_1") (pintype "passive"))
      (node (ref "C11") (pin "1") (pinfunction "1_1") (pintype "passive"))
      (node (ref "C12") (pin "1") (pinfunction "1_1") (pintype "passive"))
      (node (ref "C13") (pin "2") (pintype "passive"))
      (node (ref "C14") (pin "2") (pintype "passive"))
      (node (ref "C15") (pin "2") (pintype "passive"))
      (node (ref "C16") (pin "2") (pintype "passive"))
      (node (ref "C17") (pin "2") (pintype "passive"))
      (node (ref "C18") (pin "2") (pintype "passive"))
      (node (ref "C19") (pin "2") (pintype "passive"))
      (node (ref "C2") (pin "-") (pinfunction "-_-") (pintype "passive"))
      (node (ref "C20") (pin "2") (pintype "passive"))
      (node (ref "C21") (pin "2") (pintype "passive"))
      (node (ref "C23") (pin "2") (pintype "passive"))
      (node (ref "C24") (pin "2") (pintype "passive"))
      (node (ref "C25") (pin "2") (pintype "passive"))
      (node (ref "C27") (pin "2") (pintype "passive"))
      (node (ref "C28") (pin "2") (pintype "passive"))
      (node (ref "C29") (pin "2") (pintype "passive"))
      (node (ref "C3") (pin "1") (pinfunction "1_1") (pintype "passive"))
      (node (ref "C30") (pin "2") (pintype "passive"))
      (node (ref "C31") (pin "2") (pintype "passive"))
      (node (ref "C32") (pin "2") (pintype "passive"))
      (node (ref "C33") (pin "2") (pintype "passive"))
      (node (ref "C34") (pin "2") (pintype "passive"))
      (node (ref "C35") (pin "2") (pintype "passive"))
      (node (ref "C36") (pin "2") (pintype "passive"))
      (node (ref "C37") (pin "2") (pintype "passive"))
      (node (ref "C38") (pin "2") (pintype "passive"))
      (node (ref "C39") (pin "2") (pintype "passive"))
      (node (ref "C4") (pin "1") (pinfunction "1_1") (pintype "passive"))
      (node (ref "C41") (pin "2") (pintype "passive"))
      (node (ref "C42") (pin "2") (pintype "passive"))
      (node (ref "C43") (pin "2") (pintype "passive"))
      (node (ref "C44") (pin "2") (pintype "passive"))
      (node (ref "C45") (pin "2") (pintype "passive"))
      (node (ref "C46") (pin "2") (pintype "passive"))
      (node (ref "C47") (pin "2") (pintype "passive"))
      (node (ref "C48") (pin "2") (pintype "passive"))
      (node (ref "C49") (pin "2") (pintype "passive"))
      (node (ref "C5") (pin "1") (pinfunction "1_1") (pintype "passive"))
      (node (ref "C50") (pin "2") (pintype "passive"))
      (node (ref "C51") (pin "2") (pintype "passive"))
      (node (ref "C52") (pin "2") (pintype "passive"))
      (node (ref "C53") (pin "2") (pintype "passive"))
      (node (ref "C54") (pin "2") (pintype "passive"))
      (node (ref "C55") (pin "2") (pintype "passive"))
      (node (ref "C57") (pin "2") (pintype "passive"))
      (node (ref "C58") (pin "2") (pintype "passive"))
      (node (ref "C6") (pin "1") (pinfunction "1_1") (pintype "passive"))
      (node (ref "C60") (pin "2") (pintype "passive"))
      (node (ref "C61") (pin "2") (pintype "passive"))
      (node (ref "C63") (pin "2") (pintype "passive"))
      (node (ref "C64") (pin "2") (pintype "passive"))
      (node (ref "C65") (pin "2") (pintype "passive"))
      (node (ref "C66") (pin "2") (pintype "passive"))
      (node (ref "C67") (pin "2") (pintype "passive"))
      (node (ref "C68") (pin "2") (pintype "passive"))
      (node (ref "C7") (pin "1") (pinfunction "1_1") (pintype "passive"))
      (node (ref "C70") (pin "2") (pintype "passive"))
      (node (ref "C71") (pin "2") (pintype "passive"))
      (node (ref "C73") (pin "2") (pintype "passive"))
      (node (ref "C74") (pin "2") (pintype "passive"))
      (node (ref "C75") (pin "2") (pintype "passive"))
      (node (ref "C8") (pin "1") (pinfunction "1_1") (pintype "passive"))
      (node (ref "C9") (pin "1") (pinfunction "1_1") (pintype "passive"))
      (node (ref "J2") (pin "1") (pinfunction "1_1") (pintype "passive"))
      (node (ref "R10") (pin "2") (pinfunction "2_2") (pintype "passive"))
      (node (ref "R2") (pin "2") (pinfunction "2_2") (pintype "passive"))
      (node (ref "R21") (pin "2") (pinfunction "2_2") (pintype "passive"))
      (node (ref "R7") (pin "2") (pinfunction "2_2") (pintype "passive"))
      (node (ref "R8") (pin "2") (pinfunction "2_2") (pintype "passive"))
      (node (ref "R9") (pin "2") (pinfunction "2_2") (pintype "passive"))
      (node (ref "S1") (pin "1") (pinfunction "1_1") (pintype "passive"))
      (node (ref "S1") (pin "4") (pinfunction "4_4") (pintype "passive"))
      (node (ref "S2") (pin "1") (pinfunction "1_1") (pintype "passive"))
      (node (ref "S2") (pin "4") (pinfunction "4_4") (pintype "passive"))
      (node (ref "S3") (pin "1") (pinfunction "1_1") (pintype "passive"))
      (node (ref "S3") (pin "2") (pinfunction "2_2") (pintype "passive"))
      (node (ref "S3") (pin "3") (pinfunction "3_3") (pintype "passive"))
      (node (ref "S3") (pin "4") (pinfunction "4_4") (pintype "passive"))
      (node (ref "S4") (pin "1") (pinfunction "1_1") (pintype "passive"))
      (node (ref "S4") (pin "2") (pinfunction "2_2") (pintype "passive"))
      (node (ref "S4") (pin "3") (pinfunction "3_3") (pintype "passive"))
      (node (ref "S4") (pin "4") (pinfunction "4_4") (pintype "passive"))
      (node (ref "U1") (pin "3") (pinfunction "GND_3") (pintype "passive"))
      (node (ref "U1") (pin "5") (pinfunction "~ERROR_5") (pintype "passive"))
      (node (ref "U1") (pin "6") (pinfunction "16_6") (pintype "passive"))
      (node (ref "U11") (pin "2") (pinfunction "GND_2") (pintype "power_in"))
      (node (ref "U13") (pin "2") (pinfunction "GND_2") (pintype "power_in"))
      (node (ref "U15") (pin "10") (pinfunction "VSS_10") (pintype "power_in"))
      (node (ref "U15") (pin "11") (pinfunction "GND_11") (pintype "power_in"))
      (node (ref "U15") (pin "20") (pinfunction "RESETSEL_20") (pintype "passive"))
      (node (ref "U15") (pin "4") (pinfunction "VREFL_4") (pintype "input"))
      (node (ref "U16") (pin "2") (pinfunction "GND_2") (pintype "power_in"))
      (node (ref "U18") (pin "2") (pinfunction "GND_2") (pintype "power_in"))
      (node (ref "U2") (pin "3") (pinfunction "GND_3") (pintype "passive"))
      (node (ref "U2") (pin "6") (pinfunction "FIN_6") (pintype "passive"))
      (node (ref "U20") (pin "2") (pinfunction "GND_2") (pintype "power_in"))
      (node (ref "U22") (pin "13") (pinfunction "GND_13") (pintype "power_in"))
      (node (ref "U22") (pin "14") (pinfunction "GND_14") (pintype "power_in"))
      (node (ref "U22") (pin "9") (pinfunction "COM_9") (pintype "input"))
      (node (ref "U23") (pin "4") (pinfunction "GND_4") (pintype "passive"))
      (node (ref "U24") (pin "2") (pinfunction "GND_2") (pintype "power_in"))
      (node (ref "U25") (pin "4") (pinfunction "V-_4") (pintype "power_in"))
      (node (ref "U3") (pin "3") (pinfunction "GND_3") (pintype "passive"))
      (node (ref "U3") (pin "6") (pinfunction "FIN_6") (pintype "passive"))
      (node (ref "U4") (pin "3") (pinfunction "GND_3") (pintype "passive"))
      (node (ref "U4") (pin "6") (pinfunction "FIN_6") (pintype "passive"))
      (node (ref "U5") (pin "3") (pinfunction "GND_3") (pintype "passive"))
      (node (ref "U5") (pin "6") (pinfunction "FIN_6") (pintype "passive"))
      (node (ref "U6") (pin "4") (pinfunction "GND_4") (pintype "passive"))
      (node (ref "U7") (pin "10") (pinfunction "VSS_10") (pintype "power_in"))
      (node (ref "U7") (pin "11") (pinfunction "GND_11") (pintype "power_in"))
      (node (ref "U7") (pin "20") (pinfunction "RESETSEL_20") (pintype "passive"))
      (node (ref "U7") (pin "4") (pinfunction "VREFL_4") (pintype "input"))
      (node (ref "U8") (pin "10") (pinfunction "VSS_10") (pintype "power_in"))
      (node (ref "U8") (pin "11") (pinfunction "GND_11") (pintype "power_in"))
      (node (ref "U8") (pin "20") (pinfunction "RESETSEL_20") (pintype "passive"))
      (node (ref "U8") (pin "4") (pinfunction "VREFL_4") (pintype "input"))
      (node (ref "U9") (pin "2") (pinfunction "GND_2") (pintype "power_in"))
    )
    (net (code "119") (name "LCVDD") (class "Default")
      (node (ref "C42") (pin "1") (pintype "passive"))
      (node (ref "C45") (pin "1") (pintype "passive"))
      (node (ref "C8") (pin "2") (pinfunction "2_2") (pintype "passive"))
      (node (ref "J11") (pin "6") (pinfunction "6_6") (pintype "passive"))
      (node (ref "J6") (pin "1") (pinfunction "1_1") (pintype "passive"))
      (node (ref "R4") (pin "1") (pinfunction "1_1") (pintype "passive"))
      (node (ref "U3") (pin "4") (pinfunction "VO_4") (pintype "output"))
    )
    (net (code "120") (name "Net-(LED1-PadK)") (class "Default")
      (node (ref "LED1") (pin "K") (pinfunction "K_K") (pintype "passive"))
      (node (ref "R2") (pin "1") (pinfunction "1_1") (pintype "passive"))
    )
    (net (code "121") (name "Net-(U1-~SD)") (class "Default")
      (node (ref "R1") (pin "1") (pinfunction "1_1") (pintype "passive"))
      (node (ref "U1") (pin "1") (pinfunction "~SD_1") (pintype "passive"))
    )
    (net (code "122") (name "Net-(U2-ADJ)") (class "Default")
      (node (ref "R3") (pin "2") (pinfunction "2_2") (pintype "passive"))
      (node (ref "R7") (pin "1") (pinfunction "1_1") (pintype "passive"))
      (node (ref "U2") (pin "5") (pinfunction "ADJ_5") (pintype "bidirectional"))
    )
    (net (code "123") (name "Net-(U3-ADJ)") (class "Default")
      (node (ref "R4") (pin "2") (pinfunction "2_2") (pintype "passive"))
      (node (ref "R8") (pin "1") (pinfunction "1_1") (pintype "passive"))
      (node (ref "U3") (pin "5") (pinfunction "ADJ_5") (pintype "bidirectional"))
    )
    (net (code "124") (name "Net-(U4-ADJ)") (class "Default")
      (node (ref "R5") (pin "2") (pinfunction "2_2") (pintype "passive"))
      (node (ref "R9") (pin "1") (pinfunction "1_1") (pintype "passive"))
      (node (ref "U4") (pin "5") (pinfunction "ADJ_5") (pintype "bidirectional"))
    )
    (net (code "125") (name "Net-(U5-ADJ)") (class "Default")
      (node (ref "R10") (pin "1") (pinfunction "1_1") (pintype "passive"))
      (node (ref "R6") (pin "2") (pinfunction "2_2") (pintype "passive"))
      (node (ref "U5") (pin "5") (pinfunction "ADJ_5") (pintype "bidirectional"))
    )
    (net (code "126") (name "Net-(U10-BASE)") (class "Default")
      (node (ref "C22") (pin "2") (pintype "passive"))
      (node (ref "U10") (pin "1") (pinfunction "BASE_1") (pintype "passive"))
      (node (ref "U9") (pin "1") (pinfunction "OUT_1") (pintype "output"))
    )
    (net (code "127") (name "Net-(U10-EMITTER)") (class "Default")
      (node (ref "C22") (pin "1") (pintype "passive"))
      (node (ref "R11") (pin "2") (pinfunction "2_2") (pintype "passive"))
      (node (ref "U10") (pin "2") (pinfunction "EMITTER_2") (pintype "passive"))
      (node (ref "U9") (pin "4") (pinfunction "IN-_4") (pintype "input"))
    )
    (net (code "128") (name "Net-(U11-IN-)") (class "Default")
      (node (ref "C26") (pin "1") (pintype "passive"))
      (node (ref "R12") (pin "2") (pinfunction "2_2") (pintype "passive"))
      (node (ref "U11") (pin "4") (pinfunction "IN-_4") (pintype "input"))
      (node (ref "U12") (pin "2") (pinfunction "EMITTER_2") (pintype "passive"))
    )
    (net (code "129") (name "Net-(U11-OUT)") (class "Default")
      (node (ref "C26") (pin "2") (pintype "passive"))
      (node (ref "U11") (pin "1") (pinfunction "OUT_1") (pintype "output"))
      (node (ref "U12") (pin "1") (pinfunction "BASE_1") (pintype "passive"))
    )
    (net (code "130") (name "Net-(U13-IN-)") (class "Default")
      (node (ref "C40") (pin "1") (pintype "passive"))
      (node (ref "R13") (pin "2") (pinfunction "2_2") (pintype "passive"))
      (node (ref "U13") (pin "4") (pinfunction "IN-_4") (pintype "input"))
      (node (ref "U14") (pin "2") (pinfunction "EMITTER_2") (pintype "passive"))
    )
    (net (code "131") (name "Net-(U13-OUT)") (class "Default")
      (node (ref "C40") (pin "2") (pintype "passive"))
      (node (ref "U13") (pin "1") (pinfunction "OUT_1") (pintype "output"))
      (node (ref "U14") (pin "1") (pinfunction "BASE_1") (pintype "passive"))
    )
    (net (code "132") (name "Net-(U16-IN-)") (class "Default")
      (node (ref "C56") (pin "1") (pintype "passive"))
      (node (ref "R14") (pin "2") (pinfunction "2_2") (pintype "passive"))
      (node (ref "U16") (pin "4") (pinfunction "IN-_4") (pintype "input"))
      (node (ref "U17") (pin "2") (pinfunction "EMITTER_2") (pintype "passive"))
    )
    (net (code "133") (name "Net-(U16-OUT)") (class "Default")
      (node (ref "C56") (pin "2") (pintype "passive"))
      (node (ref "U16") (pin "1") (pinfunction "OUT_1") (pintype "output"))
      (node (ref "U17") (pin "1") (pinfunction "BASE_1") (pintype "passive"))
    )
    (net (code "134") (name "Net-(U18-IN-)") (class "Default")
      (node (ref "C59") (pin "1") (pintype "passive"))
      (node (ref "R15") (pin "2") (pinfunction "2_2") (pintype "passive"))
      (node (ref "U18") (pin "4") (pinfunction "IN-_4") (pintype "input"))
      (node (ref "U19") (pin "2") (pinfunction "EMITTER_2") (pintype "passive"))
    )
    (net (code "135") (name "Net-(U18-OUT)") (class "Default")
      (node (ref "C59") (pin "2") (pintype "passive"))
      (node (ref "U18") (pin "1") (pinfunction "OUT_1") (pintype "output"))
      (node (ref "U19") (pin "1") (pinfunction "BASE_1") (pintype "passive"))
    )
    (net (code "136") (name "Net-(U20-IN-)") (class "Default")
      (node (ref "C62") (pin "1") (pintype "passive"))
      (node (ref "R16") (pin "2") (pinfunction "2_2") (pintype "passive"))
      (node (ref "U20") (pin "4") (pinfunction "IN-_4") (pintype "input"))
      (node (ref "U21") (pin "2") (pinfunction "EMITTER_2") (pintype "passive"))
    )
    (net (code "137") (name "Net-(U20-OUT)") (class "Default")
      (node (ref "C62") (pin "2") (pintype "passive"))
      (node (ref "U20") (pin "1") (pinfunction "OUT_1") (pintype "output"))
      (node (ref "U21") (pin "1") (pinfunction "BASE_1") (pintype "passive"))
    )
    (net (code "138") (name "Net-(U24-IN+)") (class "Default")
      (node (ref "C73") (pin "1") (pintype "passive"))
      (node (ref "R20") (pin "2") (pinfunction "2_2") (pintype "passive"))
      (node (ref "R21") (pin "1") (pinfunction "1_1") (pintype "passive"))
      (node (ref "U24") (pin "3") (pinfunction "IN+_3") (pintype "input"))
    )
    (net (code "139") (name "Net-(U24-IN-)") (class "Default")
      (node (ref "C72") (pin "2") (pinfunction "2_2") (pintype "passive"))
      (node (ref "R17") (pin "1") (pinfunction "1_1") (pintype "passive"))
      (node (ref "R19") (pin "2") (pinfunction "2_2") (pintype "passive"))
      (node (ref "U24") (pin "4") (pinfunction "IN-_4") (pintype "input"))
    )
    (net (code "140") (name "VDD") (class "Default")
      (node (ref "C12") (pin "2") (pinfunction "2_2") (pintype "passive"))
      (node (ref "C37") (pin "1") (pintype "passive"))
      (node (ref "C39") (pin "1") (pintype "passive"))
      (node (ref "C43") (pin "1") (pintype "passive"))
      (node (ref "C46") (pin "1") (pintype "passive"))
      (node (ref "J11") (pin "5") (pinfunction "5_5") (pintype "passive"))
      (node (ref "J12") (pin "18") (pinfunction "18_18") (pintype "passive"))
      (node (ref "J3") (pin "1") (pinfunction "1_1") (pintype "passive"))
      (node (ref "R6") (pin "1") (pinfunction "1_1") (pintype "passive"))
      (node (ref "U5") (pin "4") (pinfunction "VO_4") (pintype "output"))
    )
    (net (code "141") (name "VDDPST") (class "Default")
      (node (ref "C1") (pin "+") (pinfunction "+_+") (pintype "passive"))
      (node (ref "C36") (pin "1") (pintype "passive"))
      (node (ref "C38") (pin "1") (pintype "passive"))
      (node (ref "C49") (pin "1") (pintype "passive"))
      (node (ref "C51") (pin "1") (pintype "passive"))
      (node (ref "J11") (pin "4") (pinfunction "4_4") (pintype "passive"))
      (node (ref "J12") (pin "15") (pinfunction "15_15") (pintype "passive"))
      (node (ref "L1") (pin "1") (pinfunction "1_1") (pintype "passive"))
    )
    (net (code "142") (name "VDD_2P5V") (class "Default")
      (node (ref "C4") (pin "2") (pinfunction "2_2") (pintype "passive"))
      (node (ref "R11") (pin "1") (pinfunction "1_1") (pintype "passive"))
      (node (ref "R12") (pin "1") (pinfunction "1_1") (pintype "passive"))
      (node (ref "R13") (pin "1") (pinfunction "1_1") (pintype "passive"))
      (node (ref "R14") (pin "1") (pinfunction "1_1") (pintype "passive"))
      (node (ref "R15") (pin "1") (pinfunction "1_1") (pintype "passive"))
      (node (ref "R16") (pin "1") (pinfunction "1_1") (pintype "passive"))
      (node (ref "R20") (pin "1") (pinfunction "1_1") (pintype "passive"))
      (node (ref "U1") (pin "4") (pinfunction "Vout_4") (pintype "output"))
    )
    (net (code "143") (name "VDD_5V_IN") (class "Default")
      (node (ref "C11") (pin "2") (pinfunction "2_2") (pintype "passive"))
      (node (ref "C13") (pin "1") (pintype "passive"))
      (node (ref "C14") (pin "1") (pintype "passive"))
      (node (ref "C15") (pin "1") (pintype "passive"))
      (node (ref "C16") (pin "1") (pintype "passive"))
      (node (ref "C18") (pin "1") (pintype "passive"))
      (node (ref "C19") (pin "1") (pintype "passive"))
      (node (ref "C2") (pin "+") (pinfunction "+_+") (pintype "passive"))
      (node (ref "C20") (pin "1") (pintype "passive"))
      (node (ref "C21") (pin "1") (pintype "passive"))
      (node (ref "C24") (pin "1") (pintype "passive"))
      (node (ref "C25") (pin "1") (pintype "passive"))
      (node (ref "C3") (pin "2") (pinfunction "2_2") (pintype "passive"))
      (node (ref "C31") (pin "1") (pintype "passive"))
      (node (ref "C32") (pin "1") (pintype "passive"))
      (node (ref "C47") (pin "1") (pintype "passive"))
      (node (ref "C48") (pin "1") (pintype "passive"))
      (node (ref "C5") (pin "2") (pinfunction "2_2") (pintype "passive"))
      (node (ref "C53") (pin "1") (pintype "passive"))
      (node (ref "C54") (pin "1") (pintype "passive"))
      (node (ref "C57") (pin "1") (pintype "passive"))
      (node (ref "C58") (pin "1") (pintype "passive"))
      (node (ref "C60") (pin "1") (pintype "passive"))
      (node (ref "C61") (pin "1") (pintype "passive"))
      (node (ref "C63") (pin "1") (pintype "passive"))
      (node (ref "C64") (pin "1") (pintype "passive"))
      (node (ref "C65") (pin "1") (pintype "passive"))
      (node (ref "C66") (pin "1") (pintype "passive"))
      (node (ref "C67") (pin "1") (pintype "passive"))
      (node (ref "C68") (pin "1") (pintype "passive"))
      (node (ref "C7") (pin "2") (pinfunction "2_2") (pintype "passive"))
      (node (ref "C70") (pin "1") (pintype "passive"))
      (node (ref "C71") (pin "1") (pintype "passive"))
      (node (ref "C9") (pin "2") (pinfunction "2_2") (pintype "passive"))
      (node (ref "J1") (pin "1") (pinfunction "1_1") (pintype "passive"))
      (node (ref "L1") (pin "2") (pinfunction "2_2") (pintype "passive"))
      (node (ref "LED1") (pin "A") (pinfunction "A_A") (pintype "passive"))
      (node (ref "R1") (pin "2") (pinfunction "2_2") (pintype "passive"))
      (node (ref "S1") (pin "3") (pinfunction "3_3") (pintype "passive"))
      (node (ref "S1") (pin "6") (pinfunction "6_6") (pintype "passive"))
      (node (ref "S2") (pin "3") (pinfunction "3_3") (pintype "passive"))
      (node (ref "S2") (pin "6") (pinfunction "6_6") (pintype "passive"))
      (node (ref "S3") (pin "6") (pinfunction "6_6") (pintype "passive"))
      (node (ref "S4") (pin "6") (pinfunction "6_6") (pintype "passive"))
      (node (ref "U1") (pin "2") (pinfunction "Vin_2") (pintype "input"))
      (node (ref "U11") (pin "5") (pinfunction "VDD_5") (pintype "power_in"))
      (node (ref "U13") (pin "5") (pinfunction "VDD_5") (pintype "power_in"))
      (node (ref "U15") (pin "1") (pinfunction "VDD_1") (pintype "power_in"))
      (node (ref "U16") (pin "5") (pinfunction "VDD_5") (pintype "power_in"))
      (node (ref "U18") (pin "5") (pinfunction "VDD_5") (pintype "power_in"))
      (node (ref "U2") (pin "2") (pinfunction "VCC_2") (pintype "power_in"))
      (node (ref "U20") (pin "5") (pinfunction "VDD_5") (pintype "power_in"))
      (node (ref "U22") (pin "10") (pinfunction "*SHDN_10") (pintype "passive"))
      (node (ref "U22") (pin "12") (pinfunction "VCC+_12") (pintype "power_in"))
      (node (ref "U22") (pin "20") (pinfunction "VCC+_20") (pintype "power_in"))
      (node (ref "U23") (pin "2") (pinfunction "VIN_2") (pintype "input"))
      (node (ref "U24") (pin "5") (pinfunction "VDD_5") (pintype "power_in"))
      (node (ref "U25") (pin "7") (pinfunction "V+_7") (pintype "power_in"))
      (node (ref "U3") (pin "2") (pinfunction "VCC_2") (pintype "power_in"))
      (node (ref "U4") (pin "2") (pinfunction "VCC_2") (pintype "power_in"))
      (node (ref "U5") (pin "2") (pinfunction "VCC_2") (pintype "power_in"))
      (node (ref "U6") (pin "2") (pinfunction "VIN_2") (pintype "input"))
      (node (ref "U7") (pin "1") (pinfunction "VDD_1") (pintype "power_in"))
      (node (ref "U8") (pin "1") (pinfunction "VDD_1") (pintype "power_in"))
      (node (ref "U9") (pin "5") (pinfunction "VDD_5") (pintype "power_in"))
    )
    (net (code "144") (name "unconnected-(C33-Pad1)") (class "Default")
      (node (ref "C33") (pin "1") (pintype "passive"))
    )
    (net (code "145") (name "unconnected-(C34-Pad1)") (class "Default")
      (node (ref "C34") (pin "1") (pintype "passive"))
    )
    (net (code "146") (name "unconnected-(C35-Pad1)") (class "Default")
      (node (ref "C35") (pin "1") (pintype "passive"))
    )
    (net (code "147") (name "unconnected-(S1-Pad2)") (class "Default")
      (node (ref "S1") (pin "2") (pinfunction "2_2") (pintype "passive"))
    )
    (net (code "148") (name "unconnected-(S2-Pad2)") (class "Default")
      (node (ref "S2") (pin "2") (pinfunction "2_2") (pintype "passive"))
    )
    (net (code "149") (name "unconnected-(U2-CTL-Pad1)") (class "Default")
      (node (ref "U2") (pin "1") (pinfunction "CTL_1") (pintype "output"))
    )
    (net (code "150") (name "unconnected-(U3-CTL-Pad1)") (class "Default")
      (node (ref "U3") (pin "1") (pinfunction "CTL_1") (pintype "output"))
    )
    (net (code "151") (name "unconnected-(U4-CTL-Pad1)") (class "Default")
      (node (ref "U4") (pin "1") (pinfunction "CTL_1") (pintype "output"))
    )
    (net (code "152") (name "unconnected-(U5-CTL-Pad1)") (class "Default")
      (node (ref "U5") (pin "1") (pinfunction "CTL_1") (pintype "output"))
    )
    (net (code "153") (name "unconnected-(U6-DNC-Pad1)") (class "Default")
      (node (ref "U6") (pin "1") (pinfunction "DNC_1") (pintype "passive"))
    )
    (net (code "154") (name "unconnected-(U6-DNC-Pad8)") (class "Default")
      (node (ref "U6") (pin "8") (pinfunction "DNC_8") (pintype "passive"))
    )
    (net (code "155") (name "unconnected-(U6-NC-Pad7)") (class "Default")
      (node (ref "U6") (pin "7") (pinfunction "NC_7") (pintype "passive"))
    )
    (net (code "156") (name "unconnected-(U6-TEMP-Pad3)") (class "Default")
      (node (ref "U6") (pin "3") (pinfunction "TEMP_3") (pintype "passive"))
    )
    (net (code "157") (name "unconnected-(U6-TRIM{slash}NR-Pad5)") (class "Default")
      (node (ref "U6") (pin "5") (pinfunction "TRIM/NR_5") (pintype "passive"))
    )
    (net (code "158") (name "unconnected-(U7-NIC-Pad5)") (class "Default")
      (node (ref "U7") (pin "5") (pinfunction "NIC_5") (pintype "passive"))
    )
    (net (code "159") (name "unconnected-(U7-NIC-Pad6)") (class "Default")
      (node (ref "U7") (pin "6") (pinfunction "NIC_6") (pintype "passive"))
    )
    (net (code "160") (name "unconnected-(U7-NIC-Pad15)") (class "Default")
      (node (ref "U7") (pin "15") (pinfunction "NIC_15") (pintype "passive"))
    )
    (net (code "161") (name "unconnected-(U7-NIC-Pad16)") (class "Default")
      (node (ref "U7") (pin "16") (pinfunction "NIC_16") (pintype "passive"))
    )
    (net (code "162") (name "unconnected-(U7-NIC-Pad17)") (class "Default")
      (node (ref "U7") (pin "17") (pinfunction "NIC_17") (pintype "passive"))
    )
    (net (code "163") (name "unconnected-(U8-NIC-Pad5)") (class "Default")
      (node (ref "U8") (pin "5") (pinfunction "NIC_5") (pintype "passive"))
    )
    (net (code "164") (name "unconnected-(U8-NIC-Pad6)") (class "Default")
      (node (ref "U8") (pin "6") (pinfunction "NIC_6") (pintype "passive"))
    )
    (net (code "165") (name "unconnected-(U8-NIC-Pad15)") (class "Default")
      (node (ref "U8") (pin "15") (pinfunction "NIC_15") (pintype "passive"))
    )
    (net (code "166") (name "unconnected-(U8-NIC-Pad16)") (class "Default")
      (node (ref "U8") (pin "16") (pinfunction "NIC_16") (pintype "passive"))
    )
    (net (code "167") (name "unconnected-(U8-NIC-Pad17)") (class "Default")
      (node (ref "U8") (pin "17") (pinfunction "NIC_17") (pintype "passive"))
    )
    (net (code "168") (name "unconnected-(U8-VOUTD-Pad2)") (class "Default")
      (node (ref "U8") (pin "2") (pinfunction "VOUTD_2") (pintype "output"))
    )
    (net (code "169") (name "unconnected-(U15-NIC-Pad5)") (class "Default")
      (node (ref "U15") (pin "5") (pinfunction "NIC_5") (pintype "passive"))
    )
    (net (code "170") (name "unconnected-(U15-NIC-Pad6)") (class "Default")
      (node (ref "U15") (pin "6") (pinfunction "NIC_6") (pintype "passive"))
    )
    (net (code "171") (name "unconnected-(U15-NIC-Pad15)") (class "Default")
      (node (ref "U15") (pin "15") (pinfunction "NIC_15") (pintype "passive"))
    )
    (net (code "172") (name "unconnected-(U15-NIC-Pad16)") (class "Default")
      (node (ref "U15") (pin "16") (pinfunction "NIC_16") (pintype "passive"))
    )
    (net (code "173") (name "unconnected-(U15-NIC-Pad17)") (class "Default")
      (node (ref "U15") (pin "17") (pinfunction "NIC_17") (pintype "passive"))
    )
    (net (code "174") (name "unconnected-(U15-VOUTD-Pad2)") (class "Default")
      (node (ref "U15") (pin "2") (pinfunction "VOUTD_2") (pintype "output"))
    )
    (net (code "175") (name "unconnected-(U22-CH3-Pad4)") (class "Default")
      (node (ref "U22") (pin "4") (pinfunction "CH3_4") (pintype "input"))
    )
    (net (code "176") (name "unconnected-(U22-CH4-Pad5)") (class "Default")
      (node (ref "U22") (pin "5") (pinfunction "CH4_5") (pintype "input"))
    )
    (net (code "177") (name "unconnected-(U22-CH5-Pad6)") (class "Default")
      (node (ref "U22") (pin "6") (pinfunction "CH5_6") (pintype "input"))
    )
    (net (code "178") (name "unconnected-(U22-CH6-Pad7)") (class "Default")
      (node (ref "U22") (pin "7") (pinfunction "CH6_7") (pintype "input"))
    )
    (net (code "179") (name "unconnected-(U22-CH7-Pad8)") (class "Default")
      (node (ref "U22") (pin "8") (pinfunction "CH7_8") (pintype "input"))
    )
    (net (code "180") (name "unconnected-(U23-DNC-Pad1)") (class "Default")
      (node (ref "U23") (pin "1") (pinfunction "DNC_1") (pintype "passive"))
    )
    (net (code "181") (name "unconnected-(U23-DNC-Pad8)") (class "Default")
      (node (ref "U23") (pin "8") (pinfunction "DNC_8") (pintype "passive"))
    )
    (net (code "182") (name "unconnected-(U23-NC-Pad7)") (class "Default")
      (node (ref "U23") (pin "7") (pinfunction "NC_7") (pintype "passive"))
    )
    (net (code "183") (name "unconnected-(U23-TEMP-Pad3)") (class "Default")
      (node (ref "U23") (pin "3") (pinfunction "TEMP_3") (pintype "passive"))
    )
    (net (code "184") (name "unconnected-(U23-TRIM{slash}NR-Pad5)") (class "Default")
      (node (ref "U23") (pin "5") (pinfunction "TRIM/NR_5") (pintype "passive"))
    )
    (net (code "185") (name "unconnected-(U25-NC-Pad1)") (class "Default")
      (node (ref "U25") (pin "1") (pinfunction "NC_1") (pintype "passive"))
    )
    (net (code "186") (name "unconnected-(U25-NC-Pad5)") (class "Default")
      (node (ref "U25") (pin "5") (pinfunction "NC_5") (pintype "passive"))
    )
    (net (code "187") (name "unconnected-(U25-NC-Pad8)") (class "Default")
      (node (ref "U25") (pin "8") (pinfunction "NC_8") (pintype "passive"))
    )
  )
)
